# XibecaModule.net
KiCad netlist of a schematic drawn in EAGLE
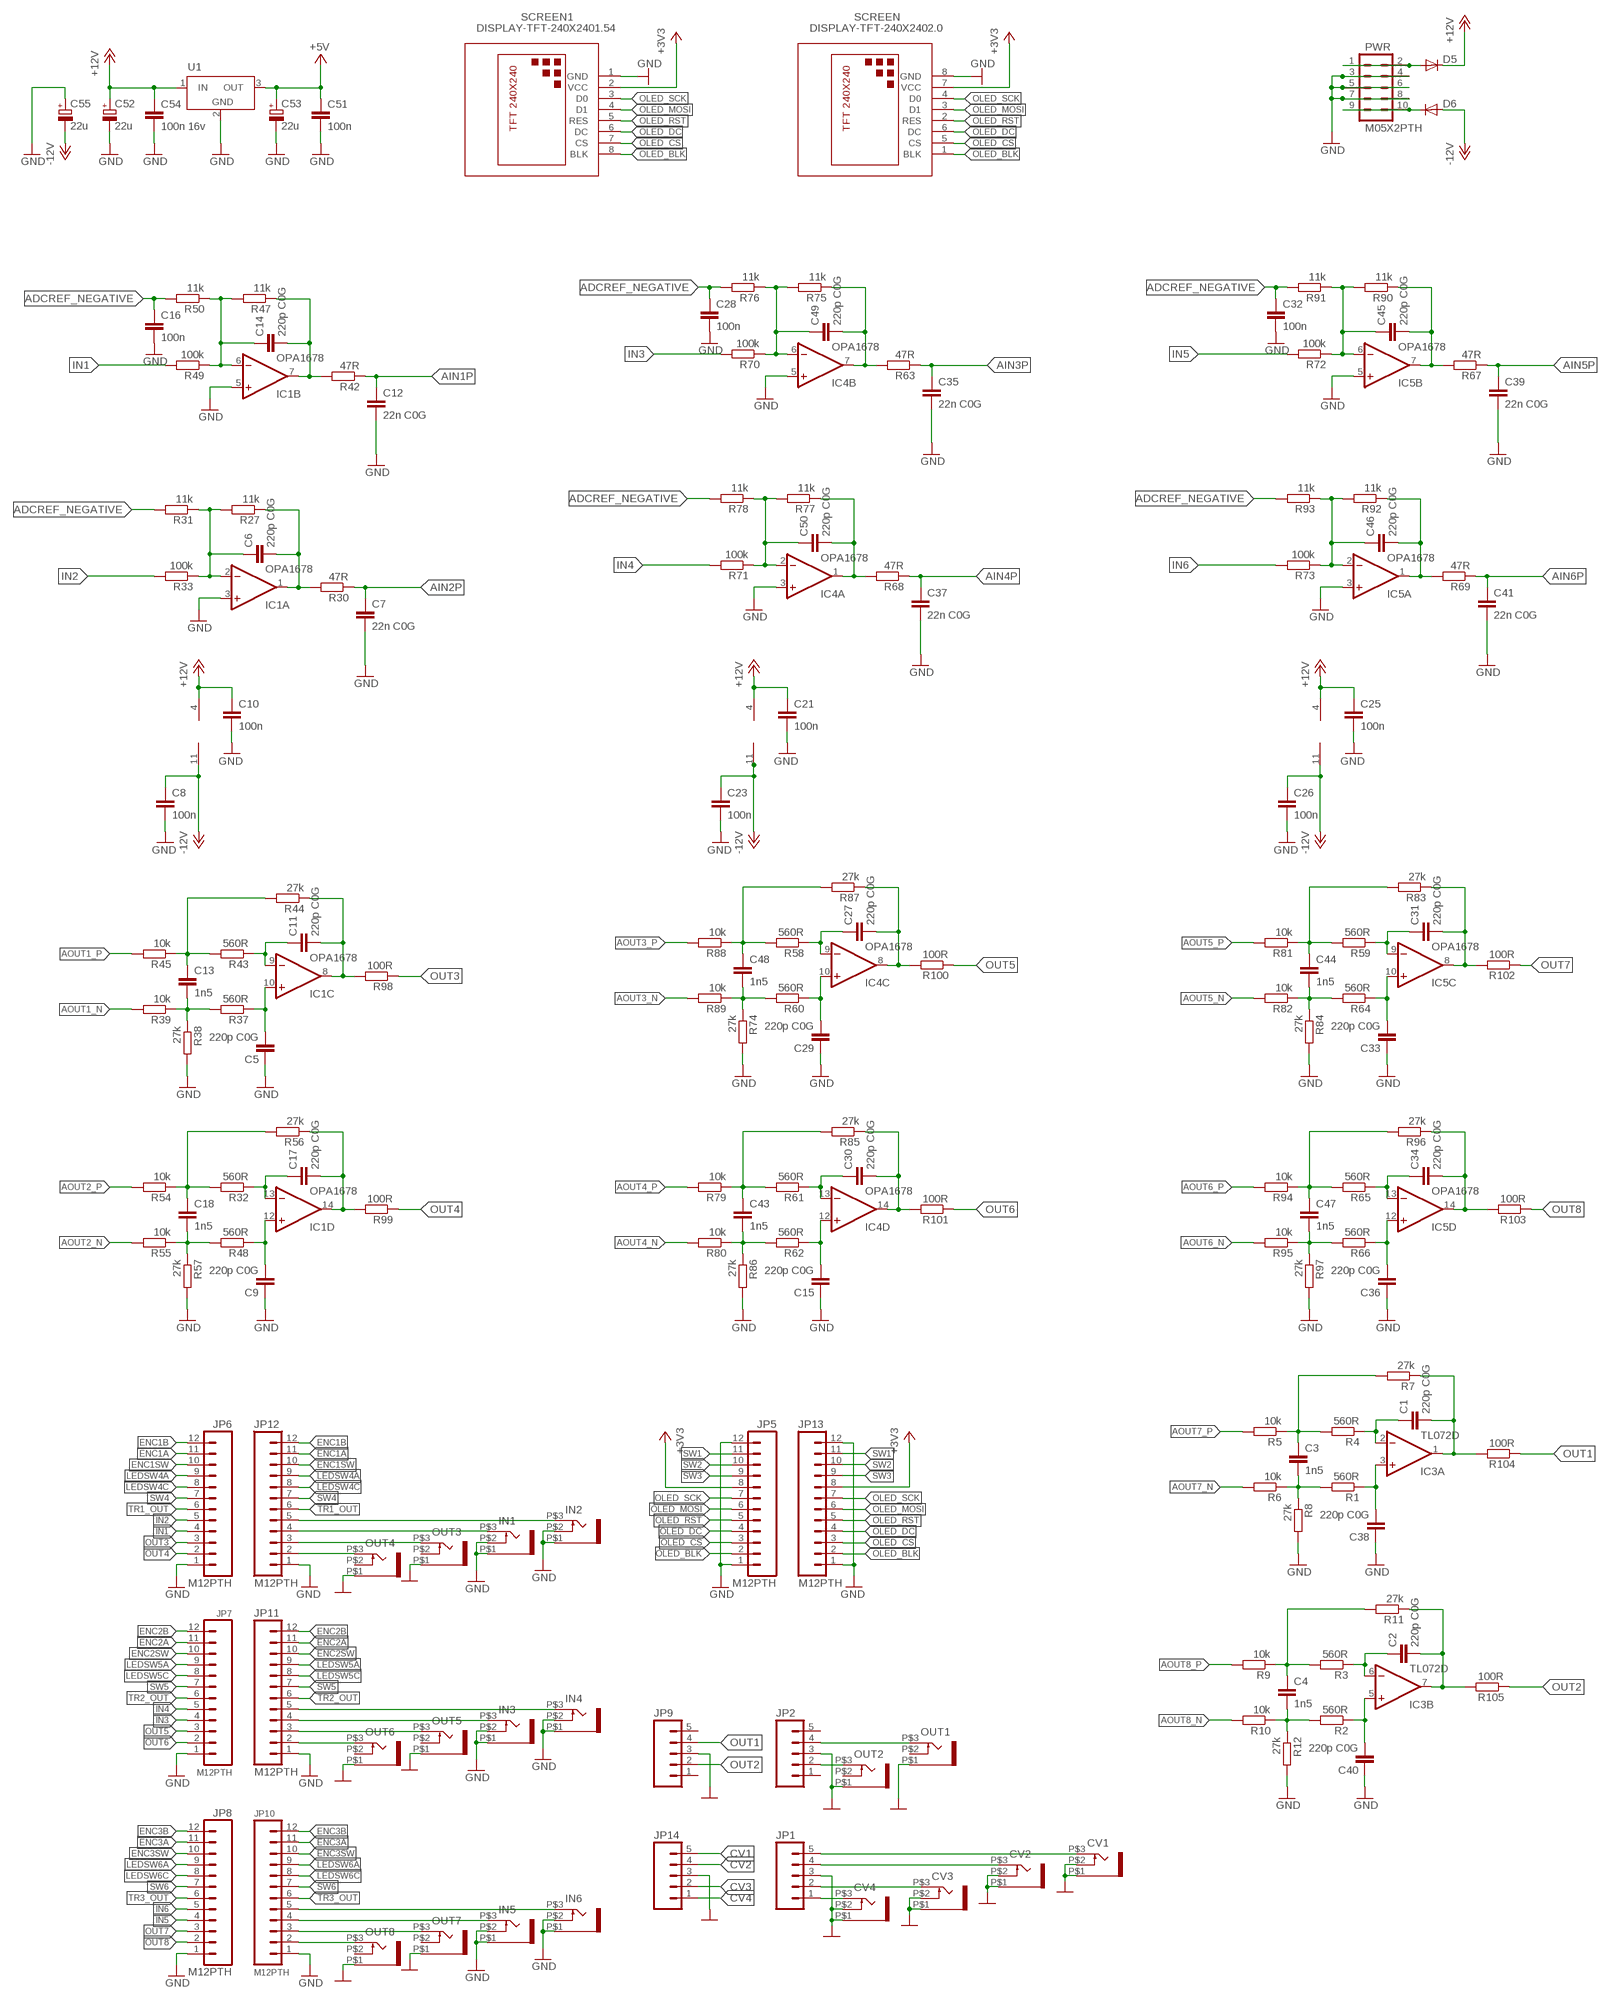
[diagram p0: schematic, sheet 1, part 1 of 2]
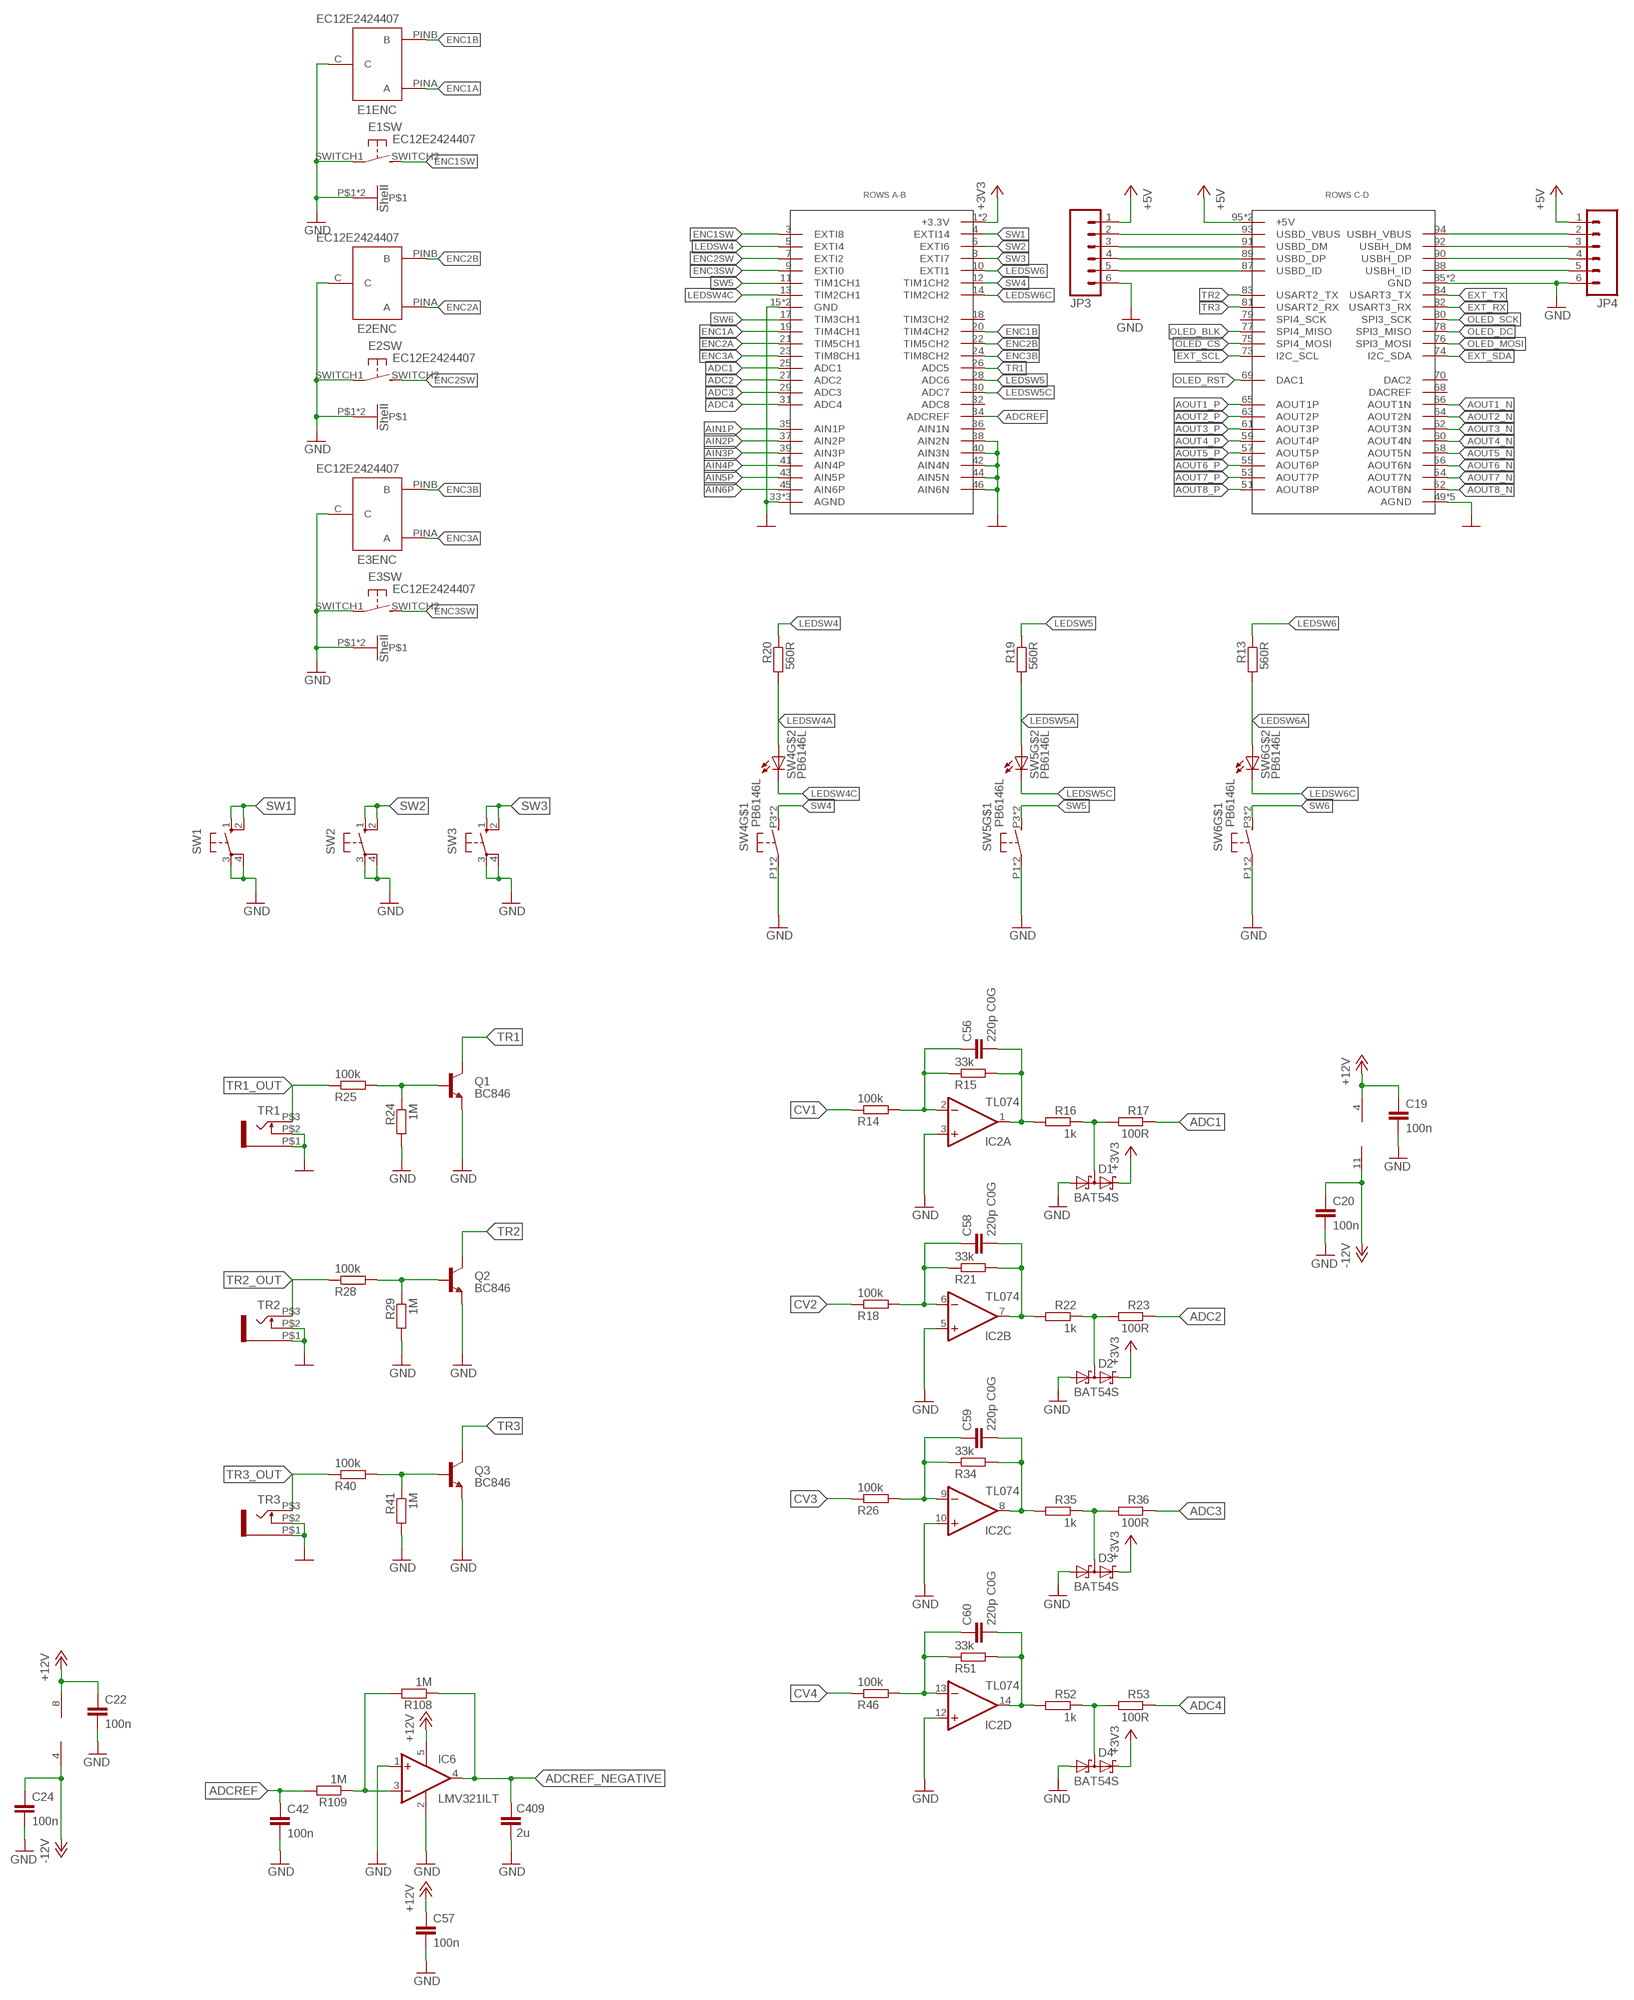
[diagram p1: schematic, sheet 1, part 2 of 2]

(export (version "E")
  (design (tool "Eeschema 10.0.6"))
  (components
    (comp (ref "C1")
      (value "220p C0G")
      (footprint "eagle-import:C0603")
      (libsource (lib "eagle-import") (part "Rebel_15457297_C-EUC0603"))
    )
    (comp (ref "C2")
      (value "220p C0G")
      (footprint "eagle-import:C0603")
      (libsource (lib "eagle-import") (part "Rebel_15457297_C-EUC0603"))
    )
    (comp (ref "C3")
      (value "1n5")
      (footprint "eagle-import:C0603")
      (libsource (lib "eagle-import") (part "Rebel_15457297_C-EUC0603"))
    )
    (comp (ref "C4")
      (value "1n5")
      (footprint "eagle-import:C0603")
      (libsource (lib "eagle-import") (part "Rebel_15457297_C-EUC0603"))
    )
    (comp (ref "C5")
      (value "220p C0G")
      (footprint "eagle-import:C0603")
      (libsource (lib "eagle-import") (part "Rebel_15457297_C-EUC0603"))
    )
    (comp (ref "C6")
      (value "220p C0G")
      (footprint "eagle-import:C0603")
      (libsource (lib "eagle-import") (part "Rebel_15457297_C-EUC0603"))
    )
    (comp (ref "C7")
      (value "22n C0G")
      (footprint "eagle-import:C0603")
      (libsource (lib "eagle-import") (part "Rebel_15457297_C-EUC0603"))
    )
    (comp (ref "C8")
      (value "100n")
      (footprint "eagle-import:C0603")
      (libsource (lib "eagle-import") (part "C-EUC0603"))
    )
    (comp (ref "C9")
      (value "220p C0G")
      (footprint "eagle-import:C0603")
      (libsource (lib "eagle-import") (part "Rebel_15457297_C-EUC0603"))
    )
    (comp (ref "C10")
      (value "100n")
      (footprint "eagle-import:C0603")
      (libsource (lib "eagle-import") (part "C-EUC0603"))
    )
    (comp (ref "C11")
      (value "220p C0G")
      (footprint "eagle-import:C0603")
      (libsource (lib "eagle-import") (part "Rebel_15457297_C-EUC0603"))
    )
    (comp (ref "C12")
      (value "22n C0G")
      (footprint "eagle-import:C0603")
      (libsource (lib "eagle-import") (part "Rebel_15457297_C-EUC0603"))
    )
    (comp (ref "C13")
      (value "1n5")
      (footprint "eagle-import:C0603")
      (libsource (lib "eagle-import") (part "Rebel_15457297_C-EUC0603"))
    )
    (comp (ref "C14")
      (value "220p C0G")
      (footprint "eagle-import:C0603")
      (libsource (lib "eagle-import") (part "Rebel_15457297_C-EUC0603"))
    )
    (comp (ref "C15")
      (value "220p C0G")
      (footprint "eagle-import:C0603")
      (libsource (lib "eagle-import") (part "Rebel_15457297_C-EUC0603"))
    )
    (comp (ref "C16")
      (value "100n")
      (footprint "eagle-import:C0603")
      (libsource (lib "eagle-import") (part "Rebel_15457297_C-EUC0603"))
    )
    (comp (ref "C17")
      (value "220p C0G")
      (footprint "eagle-import:C0603")
      (libsource (lib "eagle-import") (part "Rebel_15457297_C-EUC0603"))
    )
    (comp (ref "C18")
      (value "1n5")
      (footprint "eagle-import:C0603")
      (libsource (lib "eagle-import") (part "Rebel_15457297_C-EUC0603"))
    )
    (comp (ref "C19")
      (value "100n")
      (footprint "eagle-import:C0603")
      (libsource (lib "eagle-import") (part "Rebel_15457297_C-EUC0603"))
    )
    (comp (ref "C20")
      (value "100n")
      (footprint "eagle-import:C0603")
      (libsource (lib "eagle-import") (part "Rebel_15457297_C-EUC0603"))
    )
    (comp (ref "C21")
      (value "100n")
      (footprint "eagle-import:C0603")
      (libsource (lib "eagle-import") (part "Rebel_15457297_C-EUC0603"))
    )
    (comp (ref "C22")
      (value "100n")
      (footprint "eagle-import:C0603")
      (libsource (lib "eagle-import") (part "Rebel_15457297_C-EUC0603"))
    )
    (comp (ref "C23")
      (value "100n")
      (footprint "eagle-import:C0603")
      (libsource (lib "eagle-import") (part "Rebel_15457297_C-EUC0603"))
    )
    (comp (ref "C24")
      (value "100n")
      (footprint "eagle-import:C0603")
      (libsource (lib "eagle-import") (part "Rebel_15457297_C-EUC0603"))
    )
    (comp (ref "C25")
      (value "100n")
      (footprint "eagle-import:C0603")
      (libsource (lib "eagle-import") (part "C-EUC0603"))
    )
    (comp (ref "C26")
      (value "100n")
      (footprint "eagle-import:C0603")
      (libsource (lib "eagle-import") (part "C-EUC0603"))
    )
    (comp (ref "C27")
      (value "220p C0G")
      (footprint "eagle-import:C0603")
      (libsource (lib "eagle-import") (part "Rebel_15457297_C-EUC0603"))
    )
    (comp (ref "C28")
      (value "100n")
      (footprint "eagle-import:C0603")
      (libsource (lib "eagle-import") (part "Rebel_15457297_C-EUC0603"))
    )
    (comp (ref "C29")
      (value "220p C0G")
      (footprint "eagle-import:C0603")
      (libsource (lib "eagle-import") (part "Rebel_15457297_C-EUC0603"))
    )
    (comp (ref "C30")
      (value "220p C0G")
      (footprint "eagle-import:C0603")
      (libsource (lib "eagle-import") (part "Rebel_15457297_C-EUC0603"))
    )
    (comp (ref "C31")
      (value "220p C0G")
      (footprint "eagle-import:C0603")
      (libsource (lib "eagle-import") (part "Rebel_15457297_C-EUC0603"))
    )
    (comp (ref "C32")
      (value "100n")
      (footprint "eagle-import:C0603")
      (libsource (lib "eagle-import") (part "Rebel_15457297_C-EUC0603"))
    )
    (comp (ref "C33")
      (value "220p C0G")
      (footprint "eagle-import:C0603")
      (libsource (lib "eagle-import") (part "Rebel_15457297_C-EUC0603"))
    )
    (comp (ref "C34")
      (value "220p C0G")
      (footprint "eagle-import:C0603")
      (libsource (lib "eagle-import") (part "Rebel_15457297_C-EUC0603"))
    )
    (comp (ref "C35")
      (value "22n C0G")
      (footprint "eagle-import:C0603")
      (libsource (lib "eagle-import") (part "Rebel_15457297_C-EUC0603"))
    )
    (comp (ref "C36")
      (value "220p C0G")
      (footprint "eagle-import:C0603")
      (libsource (lib "eagle-import") (part "Rebel_15457297_C-EUC0603"))
    )
    (comp (ref "C37")
      (value "22n C0G")
      (footprint "eagle-import:C0603")
      (libsource (lib "eagle-import") (part "Rebel_15457297_C-EUC0603"))
    )
    (comp (ref "C38")
      (value "220p C0G")
      (footprint "eagle-import:C0603")
      (libsource (lib "eagle-import") (part "Rebel_15457297_C-EUC0603"))
    )
    (comp (ref "C39")
      (value "22n C0G")
      (footprint "eagle-import:C0603")
      (libsource (lib "eagle-import") (part "Rebel_15457297_C-EUC0603"))
    )
    (comp (ref "C40")
      (value "220p C0G")
      (footprint "eagle-import:C0603")
      (libsource (lib "eagle-import") (part "Rebel_15457297_C-EUC0603"))
    )
    (comp (ref "C41")
      (value "22n C0G")
      (footprint "eagle-import:C0603")
      (libsource (lib "eagle-import") (part "Rebel_15457297_C-EUC0603"))
    )
    (comp (ref "C42")
      (value "100n")
      (footprint "eagle-import:C0603")
      (libsource (lib "eagle-import") (part "Rebel_15457297_C-EUC0603"))
    )
    (comp (ref "C43")
      (value "1n5")
      (footprint "eagle-import:C0603")
      (libsource (lib "eagle-import") (part "Rebel_15457297_C-EUC0603"))
    )
    (comp (ref "C44")
      (value "1n5")
      (footprint "eagle-import:C0603")
      (libsource (lib "eagle-import") (part "Rebel_15457297_C-EUC0603"))
    )
    (comp (ref "C45")
      (value "220p C0G")
      (footprint "eagle-import:C0603")
      (libsource (lib "eagle-import") (part "Rebel_15457297_C-EUC0603"))
    )
    (comp (ref "C46")
      (value "220p C0G")
      (footprint "eagle-import:C0603")
      (libsource (lib "eagle-import") (part "Rebel_15457297_C-EUC0603"))
    )
    (comp (ref "C47")
      (value "1n5")
      (footprint "eagle-import:C0603")
      (libsource (lib "eagle-import") (part "Rebel_15457297_C-EUC0603"))
    )
    (comp (ref "C48")
      (value "1n5")
      (footprint "eagle-import:C0603")
      (libsource (lib "eagle-import") (part "Rebel_15457297_C-EUC0603"))
    )
    (comp (ref "C49")
      (value "220p C0G")
      (footprint "eagle-import:C0603")
      (libsource (lib "eagle-import") (part "Rebel_15457297_C-EUC0603"))
    )
    (comp (ref "C50")
      (value "220p C0G")
      (footprint "eagle-import:C0603")
      (libsource (lib "eagle-import") (part "Rebel_15457297_C-EUC0603"))
    )
    (comp (ref "C51")
      (value "100n")
      (footprint "eagle-import:C0603")
      (libsource (lib "eagle-import") (part "Rebel_15457297_C-EUC0603"))
    )
    (comp (ref "C52")
      (value "22u")
      (footprint "eagle-import:E5-8,5")
      (libsource (lib "eagle-import") (part "CPOL-EUE5-8.5"))
    )
    (comp (ref "C53")
      (value "22u")
      (footprint "eagle-import:E5-8,5")
      (libsource (lib "eagle-import") (part "CPOL-EUE5-8.5"))
    )
    (comp (ref "C54")
      (value "100n 16v")
      (footprint "eagle-import:C0603")
      (libsource (lib "eagle-import") (part "Rebel_15457297_C-EUC0603"))
    )
    (comp (ref "C55")
      (value "22u")
      (footprint "eagle-import:E5-8,5")
      (libsource (lib "eagle-import") (part "CPOL-EUE5-8.5"))
    )
    (comp (ref "C56")
      (value "220p C0G")
      (footprint "eagle-import:C0603")
      (libsource (lib "eagle-import") (part "Rebel_15457297_C-EUC0603"))
    )
    (comp (ref "C57")
      (value "100n")
      (footprint "eagle-import:C0603")
      (libsource (lib "eagle-import") (part "Rebel_15457297_C-EUC0603"))
    )
    (comp (ref "C58")
      (value "220p C0G")
      (footprint "eagle-import:C0603")
      (libsource (lib "eagle-import") (part "Rebel_15457297_C-EUC0603"))
    )
    (comp (ref "C59")
      (value "220p C0G")
      (footprint "eagle-import:C0603")
      (libsource (lib "eagle-import") (part "Rebel_15457297_C-EUC0603"))
    )
    (comp (ref "C60")
      (value "220p C0G")
      (footprint "eagle-import:C0603")
      (libsource (lib "eagle-import") (part "Rebel_15457297_C-EUC0603"))
    )
    (comp (ref "C409")
      (value "2u")
      (footprint "eagle-import:C0603")
      (libsource (lib "eagle-import") (part "C-EUC0603"))
    )
    (comp (ref "CV1")
      (value "THONKICONN")
      (footprint "eagle-import:THONKICONN")
      (libsource (lib "eagle-import") (part "THONKICONN"))
    )
    (comp (ref "CV2")
      (value "THONKICONN")
      (footprint "eagle-import:THONKICONN")
      (libsource (lib "eagle-import") (part "THONKICONN"))
    )
    (comp (ref "CV3")
      (value "THONKICONN")
      (footprint "eagle-import:THONKICONN")
      (libsource (lib "eagle-import") (part "THONKICONN"))
    )
    (comp (ref "CV4")
      (value "THONKICONN")
      (footprint "eagle-import:THONKICONN")
      (libsource (lib "eagle-import") (part "THONKICONN"))
    )
    (comp (ref "D1")
      (value "BAT54S")
      (footprint "eagle-import:SOT23")
      (libsource (lib "eagle-import") (part "BAT54S"))
    )
    (comp (ref "D2")
      (value "BAT54S")
      (footprint "eagle-import:SOT23")
      (libsource (lib "eagle-import") (part "BAT54S"))
    )
    (comp (ref "D3")
      (value "BAT54S")
      (footprint "eagle-import:SOT23")
      (libsource (lib "eagle-import") (part "BAT54S"))
    )
    (comp (ref "D4")
      (value "BAT54S")
      (footprint "eagle-import:SOT23")
      (libsource (lib "eagle-import") (part "BAT54S"))
    )
    (comp (ref "D5")
      (value "DIODE1N4001")
      (footprint "eagle-import:DIODE-1N4001")
      (libsource (lib "eagle-import") (part "DIODE1N4001"))
    )
    (comp (ref "D6")
      (value "DIODE1N4001")
      (footprint "eagle-import:DIODE-1N4001")
      (libsource (lib "eagle-import") (part "DIODE1N4001"))
    )
    (comp (ref "E1")
      (value "EC12E2424407")
      (footprint "eagle-import:EC12E2424407")
      (libsource (lib "eagle-import") (part "EC12E2424407"))
    )
    (comp (ref "E2")
      (value "EC12E2424407")
      (footprint "eagle-import:EC12E2424407")
      (libsource (lib "eagle-import") (part "EC12E2424407"))
    )
    (comp (ref "E3")
      (value "EC12E2424407")
      (footprint "eagle-import:EC12E2424407")
      (libsource (lib "eagle-import") (part "EC12E2424407"))
    )
    (comp (ref "IC1")
      (value "OPA1678")
      (footprint "eagle-import:SO14")
      (libsource (lib "eagle-import") (part "TL074D"))
    )
    (comp (ref "IC2")
      (value "TL074")
      (footprint "eagle-import:SO14")
      (libsource (lib "eagle-import") (part "QUAD_OPAMPD"))
    )
    (comp (ref "IC3")
      (value "TL072D")
      (footprint "eagle-import:SO08")
      (libsource (lib "eagle-import") (part "TL072D"))
    )
    (comp (ref "IC4")
      (value "OPA1678")
      (footprint "eagle-import:SO14")
      (libsource (lib "eagle-import") (part "TL074D"))
    )
    (comp (ref "IC5")
      (value "OPA1678")
      (footprint "eagle-import:SO14")
      (libsource (lib "eagle-import") (part "TL074D"))
    )
    (comp (ref "IC6")
      (value "LMV321ILT")
      (footprint "eagle-import:SOT23-5")
      (libsource (lib "eagle-import") (part "LM321?MF"))
    )
    (comp (ref "IN1")
      (value "THONKICONN")
      (footprint "eagle-import:THONKICONN")
      (libsource (lib "eagle-import") (part "THONKICONN"))
    )
    (comp (ref "IN2")
      (value "THONKICONN")
      (footprint "eagle-import:THONKICONN")
      (libsource (lib "eagle-import") (part "THONKICONN"))
    )
    (comp (ref "IN3")
      (value "THONKICONN")
      (footprint "eagle-import:THONKICONN")
      (libsource (lib "eagle-import") (part "THONKICONN"))
    )
    (comp (ref "IN4")
      (value "THONKICONN")
      (footprint "eagle-import:THONKICONN")
      (libsource (lib "eagle-import") (part "THONKICONN"))
    )
    (comp (ref "IN5")
      (value "THONKICONN")
      (footprint "eagle-import:THONKICONN")
      (libsource (lib "eagle-import") (part "THONKICONN"))
    )
    (comp (ref "IN6")
      (value "THONKICONN")
      (footprint "eagle-import:THONKICONN")
      (libsource (lib "eagle-import") (part "THONKICONN"))
    )
    (comp (ref "JP1")
      (value "M05PTH")
      (footprint "eagle-import:1X05")
      (libsource (lib "eagle-import") (part "M05PTH"))
    )
    (comp (ref "JP2")
      (value "M05PTH")
      (footprint "eagle-import:1X05")
      (libsource (lib "eagle-import") (part "M05PTH"))
    )
    (comp (ref "JP3")
      (value "M06SIP")
      (footprint "eagle-import:1X06")
      (libsource (lib "eagle-import") (part "M06SIP"))
    )
    (comp (ref "JP4")
      (value "M06SIP")
      (footprint "eagle-import:1X06")
      (libsource (lib "eagle-import") (part "M06SIP"))
    )
    (comp (ref "JP5")
      (value "M12PTH")
      (footprint "eagle-import:1X12")
      (libsource (lib "eagle-import") (part "M12PTH"))
    )
    (comp (ref "JP6")
      (value "M12PTH")
      (footprint "eagle-import:1X12")
      (libsource (lib "eagle-import") (part "M12PTH"))
    )
    (comp (ref "JP7")
      (value "M12PTH")
      (footprint "eagle-import:1X12")
      (libsource (lib "eagle-import") (part "M12PTH"))
    )
    (comp (ref "JP8")
      (value "M12PTH")
      (footprint "eagle-import:1X12")
      (libsource (lib "eagle-import") (part "M12PTH"))
    )
    (comp (ref "JP9")
      (value "M05PTH")
      (footprint "eagle-import:1X05")
      (libsource (lib "eagle-import") (part "M05PTH"))
    )
    (comp (ref "JP10")
      (value "M12PTH")
      (footprint "eagle-import:1X12")
      (libsource (lib "eagle-import") (part "M12PTH"))
    )
    (comp (ref "JP11")
      (value "M12PTH")
      (footprint "eagle-import:1X12")
      (libsource (lib "eagle-import") (part "M12PTH"))
    )
    (comp (ref "JP12")
      (value "M12PTH")
      (footprint "eagle-import:1X12")
      (libsource (lib "eagle-import") (part "M12PTH"))
    )
    (comp (ref "JP13")
      (value "M12PTH")
      (footprint "eagle-import:1X12")
      (libsource (lib "eagle-import") (part "M12PTH"))
    )
    (comp (ref "JP14")
      (value "M05PTH")
      (footprint "eagle-import:1X05")
      (libsource (lib "eagle-import") (part "M05PTH"))
    )
    (comp (ref "OUT1")
      (value "THONKICONN")
      (footprint "eagle-import:THONKICONN")
      (libsource (lib "eagle-import") (part "THONKICONN"))
    )
    (comp (ref "OUT2")
      (value "THONKICONN")
      (footprint "eagle-import:THONKICONN")
      (libsource (lib "eagle-import") (part "THONKICONN"))
    )
    (comp (ref "OUT3")
      (value "THONKICONN")
      (footprint "eagle-import:THONKICONN")
      (libsource (lib "eagle-import") (part "THONKICONN"))
    )
    (comp (ref "OUT4")
      (value "THONKICONN")
      (footprint "eagle-import:THONKICONN")
      (libsource (lib "eagle-import") (part "THONKICONN"))
    )
    (comp (ref "OUT5")
      (value "THONKICONN")
      (footprint "eagle-import:THONKICONN")
      (libsource (lib "eagle-import") (part "THONKICONN"))
    )
    (comp (ref "OUT6")
      (value "THONKICONN")
      (footprint "eagle-import:THONKICONN")
      (libsource (lib "eagle-import") (part "THONKICONN"))
    )
    (comp (ref "OUT7")
      (value "THONKICONN")
      (footprint "eagle-import:THONKICONN")
      (libsource (lib "eagle-import") (part "THONKICONN"))
    )
    (comp (ref "OUT8")
      (value "THONKICONN")
      (footprint "eagle-import:THONKICONN")
      (libsource (lib "eagle-import") (part "THONKICONN"))
    )
    (comp (ref "PWR")
      (value "M05X2PTH")
      (footprint "eagle-import:AVR_ICSP")
      (libsource (lib "eagle-import") (part "M05X2PTH"))
    )
    (comp (ref "Q1")
      (value "BC846")
      (footprint "eagle-import:SOT23")
      (libsource (lib "eagle-import") (part "BC846"))
    )
    (comp (ref "Q2")
      (value "BC846")
      (footprint "eagle-import:SOT23")
      (libsource (lib "eagle-import") (part "BC846"))
    )
    (comp (ref "Q3")
      (value "BC846")
      (footprint "eagle-import:SOT23")
      (libsource (lib "eagle-import") (part "BC846"))
    )
    (comp (ref "R1")
      (value "560R")
      (footprint "eagle-import:R0603")
      (libsource (lib "eagle-import") (part "rcl_334_R-EU_R0603"))
    )
    (comp (ref "R2")
      (value "560R")
      (footprint "eagle-import:R0603")
      (libsource (lib "eagle-import") (part "rcl_334_R-EU_R0603"))
    )
    (comp (ref "R3")
      (value "560R")
      (footprint "eagle-import:R0603")
      (libsource (lib "eagle-import") (part "rcl_334_R-EU_R0603"))
    )
    (comp (ref "R4")
      (value "560R")
      (footprint "eagle-import:R0603")
      (libsource (lib "eagle-import") (part "rcl_334_R-EU_R0603"))
    )
    (comp (ref "R5")
      (value "10k")
      (footprint "eagle-import:R0603")
      (libsource (lib "eagle-import") (part "rcl_334_R-EU_R0603"))
    )
    (comp (ref "R6")
      (value "10k")
      (footprint "eagle-import:R0603")
      (libsource (lib "eagle-import") (part "rcl_334_R-EU_R0603"))
    )
    (comp (ref "R7")
      (value "27k")
      (footprint "eagle-import:R0603")
      (libsource (lib "eagle-import") (part "rcl_334_R-EU_R0603"))
    )
    (comp (ref "R8")
      (value "27k")
      (footprint "eagle-import:R0603")
      (libsource (lib "eagle-import") (part "rcl_334_R-EU_R0603"))
    )
    (comp (ref "R9")
      (value "10k")
      (footprint "eagle-import:R0603")
      (libsource (lib "eagle-import") (part "rcl_334_R-EU_R0603"))
    )
    (comp (ref "R10")
      (value "10k")
      (footprint "eagle-import:R0603")
      (libsource (lib "eagle-import") (part "rcl_334_R-EU_R0603"))
    )
    (comp (ref "R11")
      (value "27k")
      (footprint "eagle-import:R0603")
      (libsource (lib "eagle-import") (part "rcl_334_R-EU_R0603"))
    )
    (comp (ref "R12")
      (value "27k")
      (footprint "eagle-import:R0603")
      (libsource (lib "eagle-import") (part "rcl_334_R-EU_R0603"))
    )
    (comp (ref "R13")
      (value "560R")
      (footprint "eagle-import:0603")
      (libsource (lib "eagle-import") (part "R-EU_R0603"))
    )
    (comp (ref "R14")
      (value "100k")
      (footprint "eagle-import:0603")
      (libsource (lib "eagle-import") (part "R-EU_0603"))
    )
    (comp (ref "R15")
      (value "33k")
      (footprint "eagle-import:0603")
      (libsource (lib "eagle-import") (part "R-EU_0603"))
    )
    (comp (ref "R16")
      (value "1k")
      (footprint "eagle-import:0603")
      (libsource (lib "eagle-import") (part "R-EU_0603"))
    )
    (comp (ref "R17")
      (value "100R")
      (footprint "eagle-import:0603")
      (libsource (lib "eagle-import") (part "R-EU_0603"))
    )
    (comp (ref "R18")
      (value "100k")
      (footprint "eagle-import:0603")
      (libsource (lib "eagle-import") (part "R-EU_0603"))
    )
    (comp (ref "R19")
      (value "560R")
      (footprint "eagle-import:0603")
      (libsource (lib "eagle-import") (part "R-EU_R0603"))
    )
    (comp (ref "R20")
      (value "560R")
      (footprint "eagle-import:0603")
      (libsource (lib "eagle-import") (part "R-EU_R0603"))
    )
    (comp (ref "R21")
      (value "33k")
      (footprint "eagle-import:0603")
      (libsource (lib "eagle-import") (part "R-EU_0603"))
    )
    (comp (ref "R22")
      (value "1k")
      (footprint "eagle-import:0603")
      (libsource (lib "eagle-import") (part "R-EU_0603"))
    )
    (comp (ref "R23")
      (value "100R")
      (footprint "eagle-import:0603")
      (libsource (lib "eagle-import") (part "R-EU_0603"))
    )
    (comp (ref "R24")
      (value "1M")
      (footprint "eagle-import:0603")
      (libsource (lib "eagle-import") (part "R-EU_R0603"))
    )
    (comp (ref "R25")
      (value "100k")
      (footprint "eagle-import:0603")
      (libsource (lib "eagle-import") (part "R-EU_R0603"))
    )
    (comp (ref "R26")
      (value "100k")
      (footprint "eagle-import:0603")
      (libsource (lib "eagle-import") (part "R-EU_0603"))
    )
    (comp (ref "R27")
      (value "11k")
      (footprint "eagle-import:R0603")
      (libsource (lib "eagle-import") (part "rcl_334_R-EU_R0603"))
    )
    (comp (ref "R28")
      (value "100k")
      (footprint "eagle-import:0603")
      (libsource (lib "eagle-import") (part "R-EU_R0603"))
    )
    (comp (ref "R29")
      (value "1M")
      (footprint "eagle-import:0603")
      (libsource (lib "eagle-import") (part "R-EU_R0603"))
    )
    (comp (ref "R30")
      (value "47R")
      (footprint "eagle-import:R0603")
      (libsource (lib "eagle-import") (part "rcl_334_R-EU_R0603"))
    )
    (comp (ref "R31")
      (value "11k")
      (footprint "eagle-import:R0603")
      (libsource (lib "eagle-import") (part "rcl_334_R-EU_R0603"))
    )
    (comp (ref "R32")
      (value "560R")
      (footprint "eagle-import:R0603")
      (libsource (lib "eagle-import") (part "rcl_334_R-EU_R0603"))
    )
    (comp (ref "R33")
      (value "100k")
      (footprint "eagle-import:R0603")
      (libsource (lib "eagle-import") (part "rcl_334_R-EU_R0603"))
    )
    (comp (ref "R34")
      (value "33k")
      (footprint "eagle-import:0603")
      (libsource (lib "eagle-import") (part "R-EU_0603"))
    )
    (comp (ref "R35")
      (value "1k")
      (footprint "eagle-import:0603")
      (libsource (lib "eagle-import") (part "R-EU_0603"))
    )
    (comp (ref "R36")
      (value "100R")
      (footprint "eagle-import:0603")
      (libsource (lib "eagle-import") (part "R-EU_0603"))
    )
    (comp (ref "R37")
      (value "560R")
      (footprint "eagle-import:R0603")
      (libsource (lib "eagle-import") (part "rcl_334_R-EU_R0603"))
    )
    (comp (ref "R38")
      (value "27k")
      (footprint "eagle-import:R0603")
      (libsource (lib "eagle-import") (part "rcl_334_R-EU_R0603"))
    )
    (comp (ref "R39")
      (value "10k")
      (footprint "eagle-import:R0603")
      (libsource (lib "eagle-import") (part "rcl_334_R-EU_R0603"))
    )
    (comp (ref "R40")
      (value "100k")
      (footprint "eagle-import:0603")
      (libsource (lib "eagle-import") (part "R-EU_R0603"))
    )
    (comp (ref "R41")
      (value "1M")
      (footprint "eagle-import:0603")
      (libsource (lib "eagle-import") (part "R-EU_R0603"))
    )
    (comp (ref "R42")
      (value "47R")
      (footprint "eagle-import:R0603")
      (libsource (lib "eagle-import") (part "rcl_334_R-EU_R0603"))
    )
    (comp (ref "R43")
      (value "560R")
      (footprint "eagle-import:R0603")
      (libsource (lib "eagle-import") (part "rcl_334_R-EU_R0603"))
    )
    (comp (ref "R44")
      (value "27k")
      (footprint "eagle-import:R0603")
      (libsource (lib "eagle-import") (part "rcl_334_R-EU_R0603"))
    )
    (comp (ref "R45")
      (value "10k")
      (footprint "eagle-import:R0603")
      (libsource (lib "eagle-import") (part "rcl_334_R-EU_R0603"))
    )
    (comp (ref "R46")
      (value "100k")
      (footprint "eagle-import:0603")
      (libsource (lib "eagle-import") (part "R-EU_0603"))
    )
    (comp (ref "R47")
      (value "11k")
      (footprint "eagle-import:R0603")
      (libsource (lib "eagle-import") (part "rcl_334_R-EU_R0603"))
    )
    (comp (ref "R48")
      (value "560R")
      (footprint "eagle-import:R0603")
      (libsource (lib "eagle-import") (part "rcl_334_R-EU_R0603"))
    )
    (comp (ref "R49")
      (value "100k")
      (footprint "eagle-import:R0603")
      (libsource (lib "eagle-import") (part "rcl_334_R-EU_R0603"))
    )
    (comp (ref "R50")
      (value "11k")
      (footprint "eagle-import:R0603")
      (libsource (lib "eagle-import") (part "rcl_334_R-EU_R0603"))
    )
    (comp (ref "R51")
      (value "33k")
      (footprint "eagle-import:0603")
      (libsource (lib "eagle-import") (part "R-EU_0603"))
    )
    (comp (ref "R52")
      (value "1k")
      (footprint "eagle-import:0603")
      (libsource (lib "eagle-import") (part "R-EU_0603"))
    )
    (comp (ref "R53")
      (value "100R")
      (footprint "eagle-import:0603")
      (libsource (lib "eagle-import") (part "R-EU_0603"))
    )
    (comp (ref "R54")
      (value "10k")
      (footprint "eagle-import:R0603")
      (libsource (lib "eagle-import") (part "rcl_334_R-EU_R0603"))
    )
    (comp (ref "R55")
      (value "10k")
      (footprint "eagle-import:R0603")
      (libsource (lib "eagle-import") (part "rcl_334_R-EU_R0603"))
    )
    (comp (ref "R56")
      (value "27k")
      (footprint "eagle-import:R0603")
      (libsource (lib "eagle-import") (part "rcl_334_R-EU_R0603"))
    )
    (comp (ref "R57")
      (value "27k")
      (footprint "eagle-import:R0603")
      (libsource (lib "eagle-import") (part "rcl_334_R-EU_R0603"))
    )
    (comp (ref "R58")
      (value "560R")
      (footprint "eagle-import:R0603")
      (libsource (lib "eagle-import") (part "rcl_334_R-EU_R0603"))
    )
    (comp (ref "R59")
      (value "560R")
      (footprint "eagle-import:R0603")
      (libsource (lib "eagle-import") (part "rcl_334_R-EU_R0603"))
    )
    (comp (ref "R60")
      (value "560R")
      (footprint "eagle-import:R0603")
      (libsource (lib "eagle-import") (part "rcl_334_R-EU_R0603"))
    )
    (comp (ref "R61")
      (value "560R")
      (footprint "eagle-import:R0603")
      (libsource (lib "eagle-import") (part "rcl_334_R-EU_R0603"))
    )
    (comp (ref "R62")
      (value "560R")
      (footprint "eagle-import:R0603")
      (libsource (lib "eagle-import") (part "rcl_334_R-EU_R0603"))
    )
    (comp (ref "R63")
      (value "47R")
      (footprint "eagle-import:R0603")
      (libsource (lib "eagle-import") (part "rcl_334_R-EU_R0603"))
    )
    (comp (ref "R64")
      (value "560R")
      (footprint "eagle-import:R0603")
      (libsource (lib "eagle-import") (part "rcl_334_R-EU_R0603"))
    )
    (comp (ref "R65")
      (value "560R")
      (footprint "eagle-import:R0603")
      (libsource (lib "eagle-import") (part "rcl_334_R-EU_R0603"))
    )
    (comp (ref "R66")
      (value "560R")
      (footprint "eagle-import:R0603")
      (libsource (lib "eagle-import") (part "rcl_334_R-EU_R0603"))
    )
    (comp (ref "R67")
      (value "47R")
      (footprint "eagle-import:R0603")
      (libsource (lib "eagle-import") (part "rcl_334_R-EU_R0603"))
    )
    (comp (ref "R68")
      (value "47R")
      (footprint "eagle-import:R0603")
      (libsource (lib "eagle-import") (part "rcl_334_R-EU_R0603"))
    )
    (comp (ref "R69")
      (value "47R")
      (footprint "eagle-import:R0603")
      (libsource (lib "eagle-import") (part "rcl_334_R-EU_R0603"))
    )
    (comp (ref "R70")
      (value "100k")
      (footprint "eagle-import:R0603")
      (libsource (lib "eagle-import") (part "rcl_334_R-EU_R0603"))
    )
    (comp (ref "R71")
      (value "100k")
      (footprint "eagle-import:R0603")
      (libsource (lib "eagle-import") (part "rcl_334_R-EU_R0603"))
    )
    (comp (ref "R72")
      (value "100k")
      (footprint "eagle-import:R0603")
      (libsource (lib "eagle-import") (part "rcl_334_R-EU_R0603"))
    )
    (comp (ref "R73")
      (value "100k")
      (footprint "eagle-import:R0603")
      (libsource (lib "eagle-import") (part "rcl_334_R-EU_R0603"))
    )
    (comp (ref "R74")
      (value "27k")
      (footprint "eagle-import:R0603")
      (libsource (lib "eagle-import") (part "rcl_334_R-EU_R0603"))
    )
    (comp (ref "R75")
      (value "11k")
      (footprint "eagle-import:R0603")
      (libsource (lib "eagle-import") (part "rcl_334_R-EU_R0603"))
    )
    (comp (ref "R76")
      (value "11k")
      (footprint "eagle-import:R0603")
      (libsource (lib "eagle-import") (part "rcl_334_R-EU_R0603"))
    )
    (comp (ref "R77")
      (value "11k")
      (footprint "eagle-import:R0603")
      (libsource (lib "eagle-import") (part "rcl_334_R-EU_R0603"))
    )
    (comp (ref "R78")
      (value "11k")
      (footprint "eagle-import:R0603")
      (libsource (lib "eagle-import") (part "rcl_334_R-EU_R0603"))
    )
    (comp (ref "R79")
      (value "10k")
      (footprint "eagle-import:R0603")
      (libsource (lib "eagle-import") (part "rcl_334_R-EU_R0603"))
    )
    (comp (ref "R80")
      (value "10k")
      (footprint "eagle-import:R0603")
      (libsource (lib "eagle-import") (part "rcl_334_R-EU_R0603"))
    )
    (comp (ref "R81")
      (value "10k")
      (footprint "eagle-import:R0603")
      (libsource (lib "eagle-import") (part "rcl_334_R-EU_R0603"))
    )
    (comp (ref "R82")
      (value "10k")
      (footprint "eagle-import:R0603")
      (libsource (lib "eagle-import") (part "rcl_334_R-EU_R0603"))
    )
    (comp (ref "R83")
      (value "27k")
      (footprint "eagle-import:R0603")
      (libsource (lib "eagle-import") (part "rcl_334_R-EU_R0603"))
    )
    (comp (ref "R84")
      (value "27k")
      (footprint "eagle-import:R0603")
      (libsource (lib "eagle-import") (part "rcl_334_R-EU_R0603"))
    )
    (comp (ref "R85")
      (value "27k")
      (footprint "eagle-import:R0603")
      (libsource (lib "eagle-import") (part "rcl_334_R-EU_R0603"))
    )
    (comp (ref "R86")
      (value "27k")
      (footprint "eagle-import:R0603")
      (libsource (lib "eagle-import") (part "rcl_334_R-EU_R0603"))
    )
    (comp (ref "R87")
      (value "27k")
      (footprint "eagle-import:R0603")
      (libsource (lib "eagle-import") (part "rcl_334_R-EU_R0603"))
    )
    (comp (ref "R88")
      (value "10k")
      (footprint "eagle-import:R0603")
      (libsource (lib "eagle-import") (part "rcl_334_R-EU_R0603"))
    )
    (comp (ref "R89")
      (value "10k")
      (footprint "eagle-import:R0603")
      (libsource (lib "eagle-import") (part "rcl_334_R-EU_R0603"))
    )
    (comp (ref "R90")
      (value "11k")
      (footprint "eagle-import:R0603")
      (libsource (lib "eagle-import") (part "rcl_334_R-EU_R0603"))
    )
    (comp (ref "R91")
      (value "11k")
      (footprint "eagle-import:R0603")
      (libsource (lib "eagle-import") (part "rcl_334_R-EU_R0603"))
    )
    (comp (ref "R92")
      (value "11k")
      (footprint "eagle-import:R0603")
      (libsource (lib "eagle-import") (part "rcl_334_R-EU_R0603"))
    )
    (comp (ref "R93")
      (value "11k")
      (footprint "eagle-import:R0603")
      (libsource (lib "eagle-import") (part "rcl_334_R-EU_R0603"))
    )
    (comp (ref "R94")
      (value "10k")
      (footprint "eagle-import:R0603")
      (libsource (lib "eagle-import") (part "rcl_334_R-EU_R0603"))
    )
    (comp (ref "R95")
      (value "10k")
      (footprint "eagle-import:R0603")
      (libsource (lib "eagle-import") (part "rcl_334_R-EU_R0603"))
    )
    (comp (ref "R96")
      (value "27k")
      (footprint "eagle-import:R0603")
      (libsource (lib "eagle-import") (part "rcl_334_R-EU_R0603"))
    )
    (comp (ref "R97")
      (value "27k")
      (footprint "eagle-import:R0603")
      (libsource (lib "eagle-import") (part "rcl_334_R-EU_R0603"))
    )
    (comp (ref "R98")
      (value "100R")
      (footprint "eagle-import:R0603")
      (libsource (lib "eagle-import") (part "rcl_334_R-EU_R0603"))
    )
    (comp (ref "R99")
      (value "100R")
      (footprint "eagle-import:R0603")
      (libsource (lib "eagle-import") (part "rcl_334_R-EU_R0603"))
    )
    (comp (ref "R100")
      (value "100R")
      (footprint "eagle-import:R0603")
      (libsource (lib "eagle-import") (part "rcl_334_R-EU_R0603"))
    )
    (comp (ref "R101")
      (value "100R")
      (footprint "eagle-import:R0603")
      (libsource (lib "eagle-import") (part "rcl_334_R-EU_R0603"))
    )
    (comp (ref "R102")
      (value "100R")
      (footprint "eagle-import:R0603")
      (libsource (lib "eagle-import") (part "rcl_334_R-EU_R0603"))
    )
    (comp (ref "R103")
      (value "100R")
      (footprint "eagle-import:R0603")
      (libsource (lib "eagle-import") (part "rcl_334_R-EU_R0603"))
    )
    (comp (ref "R104")
      (value "100R")
      (footprint "eagle-import:R0603")
      (libsource (lib "eagle-import") (part "rcl_334_R-EU_R0603"))
    )
    (comp (ref "R105")
      (value "100R")
      (footprint "eagle-import:R0603")
      (libsource (lib "eagle-import") (part "rcl_334_R-EU_R0603"))
    )
    (comp (ref "R108")
      (value "1M")
      (footprint "eagle-import:R0603")
      (libsource (lib "eagle-import") (part "rcl_334_R-EU_R0603"))
    )
    (comp (ref "R109")
      (value "1M")
      (footprint "eagle-import:R0603")
      (libsource (lib "eagle-import") (part "rcl_334_R-EU_R0603"))
    )
    (comp (ref "SCREEN")
      (value "DISPLAY-TFT-240X2402.0")
      (footprint "eagle-import:DISPLAY-TFT-240X320-2.0_")
      (libsource (lib "eagle-import") (part "DISPLAY-TFT-240X2402.0"))
    )
    (comp (ref "SCREEN1")
      (value "DISPLAY-TFT-240X2401.54")
      (footprint "eagle-import:DISPLAY-TFT-240X240-1.54_")
      (libsource (lib "eagle-import") (part "DISPLAY-TFT-240X2401.54"))
    )
    (comp (ref "SW1")
      (value "10-XX")
      (footprint "eagle-import:B3F-10XX")
      (fields (field (name "MPN") "B3F-1000"))
      (libsource (lib "eagle-import") (part "10-XX"))
    )
    (comp (ref "SW2")
      (value "10-XX")
      (footprint "eagle-import:B3F-10XX")
      (fields (field (name "MPN") "B3F-1000"))
      (libsource (lib "eagle-import") (part "10-XX"))
    )
    (comp (ref "SW3")
      (value "10-XX")
      (footprint "eagle-import:B3F-10XX")
      (fields (field (name "MPN") "B3F-1000"))
      (libsource (lib "eagle-import") (part "10-XX"))
    )
    (comp (ref "SW4")
      (value "PB6146L")
      (footprint "eagle-import:PB6146L")
      (libsource (lib "eagle-import") (part "PB6146L"))
    )
    (comp (ref "SW5")
      (value "PB6146L")
      (footprint "eagle-import:PB6146L")
      (libsource (lib "eagle-import") (part "PB6146L"))
    )
    (comp (ref "SW6")
      (value "PB6146L")
      (footprint "eagle-import:PB6146L")
      (libsource (lib "eagle-import") (part "PB6146L"))
    )
    (comp (ref "TR1")
      (value "THONKICONN")
      (footprint "eagle-import:THONKICONN")
      (libsource (lib "eagle-import") (part "THONKICONN"))
    )
    (comp (ref "TR2")
      (value "THONKICONN")
      (footprint "eagle-import:THONKICONN")
      (libsource (lib "eagle-import") (part "THONKICONN"))
    )
    (comp (ref "TR3")
      (value "THONKICONN")
      (footprint "eagle-import:THONKICONN")
      (libsource (lib "eagle-import") (part "THONKICONN"))
    )
    (comp (ref "U$2")
      (value "NOCTUA2NOCTUA2")
      (footprint "eagle-import:NOCTUA")
      (libsource (lib "eagle-import") (part "NOCTUA2NOCTUA2"))
    )
    (comp (ref "U1")
      (value "TSR-1-2450")
      (footprint "eagle-import:TSR-1-2450")
      (libsource (lib "eagle-import") (part "TSR-1-2450"))
    )
  )
  (nets
    (net (code "1") (name "+3V3") (class "Default")
      (node (ref "D1") (pin "2") (pinfunction "C2_2") (pintype "passive"))
      (node (ref "D2") (pin "2") (pinfunction "C2_2") (pintype "passive"))
      (node (ref "D3") (pin "2") (pinfunction "C2_2") (pintype "passive"))
      (node (ref "D4") (pin "2") (pinfunction "C2_2") (pintype "passive"))
      (node (ref "JP13") (pin "8") (pinfunction "8_8") (pintype "passive"))
      (node (ref "JP5") (pin "8") (pinfunction "8_8") (pintype "passive"))
      (node (ref "SCREEN") (pin "7") (pinfunction "VCC_7") (pintype "power_in"))
      (node (ref "SCREEN1") (pin "2") (pinfunction "VCC_2") (pintype "power_in"))
      (node (ref "U$2") (pin "1") (pinfunction "+3.3V_1") (pintype "bidirectional"))
      (node (ref "U$2") (pin "2") (pinfunction "+3.3V_2") (pintype "bidirectional"))
    )
    (net (code "2") (name "+5V") (class "Default")
      (node (ref "C51") (pin "1") (pinfunction "1_1") (pintype "passive"))
      (node (ref "C53") (pin "+") (pinfunction "+_+") (pintype "passive"))
      (node (ref "JP3") (pin "1") (pinfunction "1_1") (pintype "passive"))
      (node (ref "JP4") (pin "1") (pinfunction "1_1") (pintype "passive"))
      (node (ref "U$2") (pin "95") (pinfunction "+5V_95") (pintype "bidirectional"))
      (node (ref "U$2") (pin "96") (pinfunction "+5V_96") (pintype "bidirectional"))
      (node (ref "U1") (pin "3") (pinfunction "OUT_3") (pintype "output"))
    )
    (net (code "3") (name "+12V") (class "Default")
      (node (ref "C10") (pin "1") (pinfunction "1_1") (pintype "passive"))
      (node (ref "C19") (pin "1") (pinfunction "1_1") (pintype "passive"))
      (node (ref "C21") (pin "1") (pinfunction "1_1") (pintype "passive"))
      (node (ref "C22") (pin "1") (pinfunction "1_1") (pintype "passive"))
      (node (ref "C25") (pin "1") (pinfunction "1_1") (pintype "passive"))
      (node (ref "C52") (pin "+") (pinfunction "+_+") (pintype "passive"))
      (node (ref "C54") (pin "1") (pinfunction "1_1") (pintype "passive"))
      (node (ref "C57") (pin "1") (pinfunction "1_1") (pintype "passive"))
      (node (ref "D5") (pin "C") (pinfunction "C_C") (pintype "passive"))
      (node (ref "IC1") (pin "4") (pinfunction "V+_4") (pintype "power_in"))
      (node (ref "IC2") (pin "4") (pinfunction "V+_4") (pintype "power_in"))
      (node (ref "IC3") (pin "8") (pinfunction "V+_8") (pintype "power_in"))
      (node (ref "IC4") (pin "4") (pinfunction "V+_4") (pintype "power_in"))
      (node (ref "IC5") (pin "4") (pinfunction "V+_4") (pintype "power_in"))
      (node (ref "IC6") (pin "5") (pinfunction "V+_5") (pintype "power_in"))
      (node (ref "U1") (pin "1") (pinfunction "IN_1") (pintype "input"))
    )
    (net (code "4") (name "-12V") (class "Default")
      (node (ref "C20") (pin "1") (pinfunction "1_1") (pintype "passive"))
      (node (ref "C23") (pin "1") (pinfunction "1_1") (pintype "passive"))
      (node (ref "C24") (pin "1") (pinfunction "1_1") (pintype "passive"))
      (node (ref "C26") (pin "1") (pinfunction "1_1") (pintype "passive"))
      (node (ref "C55") (pin "-") (pinfunction "-_-") (pintype "passive"))
      (node (ref "C8") (pin "1") (pinfunction "1_1") (pintype "passive"))
      (node (ref "D6") (pin "A") (pinfunction "A_A") (pintype "passive"))
      (node (ref "IC1") (pin "11") (pinfunction "V-_11") (pintype "power_in"))
      (node (ref "IC2") (pin "11") (pinfunction "V-_11") (pintype "power_in"))
      (node (ref "IC3") (pin "4") (pinfunction "V-_4") (pintype "power_in"))
      (node (ref "IC4") (pin "11") (pinfunction "V-_11") (pintype "power_in"))
      (node (ref "IC5") (pin "11") (pinfunction "V-_11") (pintype "power_in"))
    )
    (net (code "5") (name "ADC1") (class "Default")
      (node (ref "R17") (pin "1") (pinfunction "1_1") (pintype "passive"))
      (node (ref "U$2") (pin "25") (pinfunction "ADC1_25") (pintype "bidirectional"))
    )
    (net (code "6") (name "ADC2") (class "Default")
      (node (ref "R23") (pin "1") (pinfunction "1_1") (pintype "passive"))
      (node (ref "U$2") (pin "27") (pinfunction "ADC2_27") (pintype "bidirectional"))
    )
    (net (code "7") (name "ADC3") (class "Default")
      (node (ref "R36") (pin "1") (pinfunction "1_1") (pintype "passive"))
      (node (ref "U$2") (pin "29") (pinfunction "ADC3_29") (pintype "bidirectional"))
    )
    (net (code "8") (name "ADC4") (class "Default")
      (node (ref "R53") (pin "1") (pinfunction "1_1") (pintype "passive"))
      (node (ref "U$2") (pin "31") (pinfunction "ADC4_31") (pintype "bidirectional"))
    )
    (net (code "9") (name "ADCREF") (class "Default")
      (node (ref "C42") (pin "1") (pinfunction "1_1") (pintype "passive"))
      (node (ref "R109") (pin "2") (pinfunction "2_2") (pintype "passive"))
      (node (ref "U$2") (pin "34") (pinfunction "ADCREF_34") (pintype "bidirectional"))
    )
    (net (code "10") (name "ADCREF_NEGATIVE") (class "Default")
      (node (ref "C16") (pin "1") (pinfunction "1_1") (pintype "passive"))
      (node (ref "C28") (pin "1") (pinfunction "1_1") (pintype "passive"))
      (node (ref "C32") (pin "1") (pinfunction "1_1") (pintype "passive"))
      (node (ref "C409") (pin "1") (pinfunction "1_1") (pintype "passive"))
      (node (ref "IC6") (pin "4") (pinfunction "OUT_4") (pintype "output"))
      (node (ref "R108") (pin "1") (pinfunction "1_1") (pintype "passive"))
      (node (ref "R31") (pin "2") (pinfunction "2_2") (pintype "passive"))
      (node (ref "R50") (pin "2") (pinfunction "2_2") (pintype "passive"))
      (node (ref "R76") (pin "2") (pinfunction "2_2") (pintype "passive"))
      (node (ref "R78") (pin "2") (pinfunction "2_2") (pintype "passive"))
      (node (ref "R91") (pin "2") (pinfunction "2_2") (pintype "passive"))
      (node (ref "R93") (pin "2") (pinfunction "2_2") (pintype "passive"))
    )
    (net (code "11") (name "AIN1P") (class "Default")
      (node (ref "C12") (pin "1") (pinfunction "1_1") (pintype "passive"))
      (node (ref "R42") (pin "1") (pinfunction "1_1") (pintype "passive"))
      (node (ref "U$2") (pin "35") (pinfunction "AIN1P_35") (pintype "bidirectional"))
    )
    (net (code "12") (name "AIN2P") (class "Default")
      (node (ref "C7") (pin "1") (pinfunction "1_1") (pintype "passive"))
      (node (ref "R30") (pin "1") (pinfunction "1_1") (pintype "passive"))
      (node (ref "U$2") (pin "37") (pinfunction "AIN2P_37") (pintype "bidirectional"))
    )
    (net (code "13") (name "AIN3P") (class "Default")
      (node (ref "C35") (pin "1") (pinfunction "1_1") (pintype "passive"))
      (node (ref "R63") (pin "1") (pinfunction "1_1") (pintype "passive"))
      (node (ref "U$2") (pin "39") (pinfunction "AIN3P_39") (pintype "bidirectional"))
    )
    (net (code "14") (name "AIN4P") (class "Default")
      (node (ref "C37") (pin "1") (pinfunction "1_1") (pintype "passive"))
      (node (ref "R68") (pin "1") (pinfunction "1_1") (pintype "passive"))
      (node (ref "U$2") (pin "41") (pinfunction "AIN4P_41") (pintype "bidirectional"))
    )
    (net (code "15") (name "AIN5P") (class "Default")
      (node (ref "C39") (pin "1") (pinfunction "1_1") (pintype "passive"))
      (node (ref "R67") (pin "1") (pinfunction "1_1") (pintype "passive"))
      (node (ref "U$2") (pin "43") (pinfunction "AIN5P_43") (pintype "bidirectional"))
    )
    (net (code "16") (name "AIN6P") (class "Default")
      (node (ref "C41") (pin "1") (pinfunction "1_1") (pintype "passive"))
      (node (ref "R69") (pin "1") (pinfunction "1_1") (pintype "passive"))
      (node (ref "U$2") (pin "45") (pinfunction "AIN6P_45") (pintype "bidirectional"))
    )
    (net (code "17") (name "AOUT1_N") (class "Default")
      (node (ref "R39") (pin "2") (pinfunction "2_2") (pintype "passive"))
      (node (ref "U$2") (pin "66") (pinfunction "AOUT1N_66") (pintype "bidirectional"))
    )
    (net (code "18") (name "AOUT1_P") (class "Default")
      (node (ref "R45") (pin "2") (pinfunction "2_2") (pintype "passive"))
      (node (ref "U$2") (pin "65") (pinfunction "AOUT1P_65") (pintype "bidirectional"))
    )
    (net (code "19") (name "AOUT2_N") (class "Default")
      (node (ref "R55") (pin "2") (pinfunction "2_2") (pintype "passive"))
      (node (ref "U$2") (pin "64") (pinfunction "AOUT2N_64") (pintype "bidirectional"))
    )
    (net (code "20") (name "AOUT2_P") (class "Default")
      (node (ref "R54") (pin "2") (pinfunction "2_2") (pintype "passive"))
      (node (ref "U$2") (pin "63") (pinfunction "AOUT2P_63") (pintype "bidirectional"))
    )
    (net (code "21") (name "AOUT3_N") (class "Default")
      (node (ref "R89") (pin "2") (pinfunction "2_2") (pintype "passive"))
      (node (ref "U$2") (pin "62") (pinfunction "AOUT3N_62") (pintype "bidirectional"))
    )
    (net (code "22") (name "AOUT3_P") (class "Default")
      (node (ref "R88") (pin "2") (pinfunction "2_2") (pintype "passive"))
      (node (ref "U$2") (pin "61") (pinfunction "AOUT3P_61") (pintype "bidirectional"))
    )
    (net (code "23") (name "AOUT4_N") (class "Default")
      (node (ref "R80") (pin "2") (pinfunction "2_2") (pintype "passive"))
      (node (ref "U$2") (pin "60") (pinfunction "AOUT4N_60") (pintype "bidirectional"))
    )
    (net (code "24") (name "AOUT4_P") (class "Default")
      (node (ref "R79") (pin "2") (pinfunction "2_2") (pintype "passive"))
      (node (ref "U$2") (pin "59") (pinfunction "AOUT4P_59") (pintype "bidirectional"))
    )
    (net (code "25") (name "AOUT5_N") (class "Default")
      (node (ref "R82") (pin "2") (pinfunction "2_2") (pintype "passive"))
      (node (ref "U$2") (pin "58") (pinfunction "AOUT5N_58") (pintype "bidirectional"))
    )
    (net (code "26") (name "AOUT5_P") (class "Default")
      (node (ref "R81") (pin "2") (pinfunction "2_2") (pintype "passive"))
      (node (ref "U$2") (pin "57") (pinfunction "AOUT5P_57") (pintype "bidirectional"))
    )
    (net (code "27") (name "AOUT6_N") (class "Default")
      (node (ref "R95") (pin "2") (pinfunction "2_2") (pintype "passive"))
      (node (ref "U$2") (pin "56") (pinfunction "AOUT6N_56") (pintype "bidirectional"))
    )
    (net (code "28") (name "AOUT6_P") (class "Default")
      (node (ref "R94") (pin "2") (pinfunction "2_2") (pintype "passive"))
      (node (ref "U$2") (pin "55") (pinfunction "AOUT6P_55") (pintype "bidirectional"))
    )
    (net (code "29") (name "AOUT7_N") (class "Default")
      (node (ref "R6") (pin "2") (pinfunction "2_2") (pintype "passive"))
      (node (ref "U$2") (pin "54") (pinfunction "AOUT7N_54") (pintype "bidirectional"))
    )
    (net (code "30") (name "AOUT7_P") (class "Default")
      (node (ref "R5") (pin "2") (pinfunction "2_2") (pintype "passive"))
      (node (ref "U$2") (pin "53") (pinfunction "AOUT7P_53") (pintype "bidirectional"))
    )
    (net (code "31") (name "AOUT8_N") (class "Default")
      (node (ref "R10") (pin "2") (pinfunction "2_2") (pintype "passive"))
      (node (ref "U$2") (pin "52") (pinfunction "AOUT8N_52") (pintype "bidirectional"))
    )
    (net (code "32") (name "AOUT8_P") (class "Default")
      (node (ref "R9") (pin "2") (pinfunction "2_2") (pintype "passive"))
      (node (ref "U$2") (pin "51") (pinfunction "AOUT8P_51") (pintype "bidirectional"))
    )
    (net (code "33") (name "CV1") (class "Default")
      (node (ref "JP14") (pin "5") (pinfunction "5_5") (pintype "passive"))
      (node (ref "R14") (pin "1") (pinfunction "1_1") (pintype "passive"))
    )
    (net (code "34") (name "CV2") (class "Default")
      (node (ref "JP14") (pin "4") (pinfunction "4_4") (pintype "passive"))
      (node (ref "R18") (pin "1") (pinfunction "1_1") (pintype "passive"))
    )
    (net (code "35") (name "CV3") (class "Default")
      (node (ref "JP14") (pin "2") (pinfunction "2_2") (pintype "passive"))
      (node (ref "R26") (pin "1") (pinfunction "1_1") (pintype "passive"))
    )
    (net (code "36") (name "CV4") (class "Default")
      (node (ref "JP14") (pin "1") (pinfunction "1_1") (pintype "passive"))
      (node (ref "R46") (pin "1") (pinfunction "1_1") (pintype "passive"))
    )
    (net (code "37") (name "ENC1A") (class "Default")
      (node (ref "E1") (pin "PINA") (pinfunction "A_PINA") (pintype "bidirectional"))
      (node (ref "JP12") (pin "11") (pinfunction "11_11") (pintype "passive"))
      (node (ref "JP6") (pin "11") (pinfunction "11_11") (pintype "passive"))
      (node (ref "U$2") (pin "19") (pinfunction "TIM4CH1_19") (pintype "bidirectional"))
    )
    (net (code "38") (name "ENC1B") (class "Default")
      (node (ref "E1") (pin "PINB") (pinfunction "B_PINB") (pintype "bidirectional"))
      (node (ref "JP12") (pin "12") (pinfunction "12_12") (pintype "passive"))
      (node (ref "JP6") (pin "12") (pinfunction "12_12") (pintype "passive"))
      (node (ref "U$2") (pin "20") (pinfunction "TIM4CH2_20") (pintype "bidirectional"))
    )
    (net (code "39") (name "ENC1SW") (class "Default")
      (node (ref "E1") (pin "SWITCH2") (pinfunction "S_SWITCH2") (pintype "passive"))
      (node (ref "JP12") (pin "10") (pinfunction "10_10") (pintype "passive"))
      (node (ref "JP6") (pin "10") (pinfunction "10_10") (pintype "passive"))
      (node (ref "U$2") (pin "3") (pinfunction "EXTI8_3") (pintype "bidirectional"))
    )
    (net (code "40") (name "ENC2A") (class "Default")
      (node (ref "E2") (pin "PINA") (pinfunction "A_PINA") (pintype "bidirectional"))
      (node (ref "JP11") (pin "11") (pinfunction "11_11") (pintype "passive"))
      (node (ref "JP7") (pin "11") (pinfunction "11_11") (pintype "passive"))
      (node (ref "U$2") (pin "21") (pinfunction "TIM5CH1_21") (pintype "bidirectional"))
    )
    (net (code "41") (name "ENC2B") (class "Default")
      (node (ref "E2") (pin "PINB") (pinfunction "B_PINB") (pintype "bidirectional"))
      (node (ref "JP11") (pin "12") (pinfunction "12_12") (pintype "passive"))
      (node (ref "JP7") (pin "12") (pinfunction "12_12") (pintype "passive"))
      (node (ref "U$2") (pin "22") (pinfunction "TIM5CH2_22") (pintype "bidirectional"))
    )
    (net (code "42") (name "ENC2SW") (class "Default")
      (node (ref "E2") (pin "SWITCH2") (pinfunction "S_SWITCH2") (pintype "passive"))
      (node (ref "JP11") (pin "10") (pinfunction "10_10") (pintype "passive"))
      (node (ref "JP7") (pin "10") (pinfunction "10_10") (pintype "passive"))
      (node (ref "U$2") (pin "7") (pinfunction "EXTI2_7") (pintype "bidirectional"))
    )
    (net (code "43") (name "ENC3A") (class "Default")
      (node (ref "E3") (pin "PINA") (pinfunction "A_PINA") (pintype "bidirectional"))
      (node (ref "JP10") (pin "11") (pinfunction "11_11") (pintype "passive"))
      (node (ref "JP8") (pin "11") (pinfunction "11_11") (pintype "passive"))
      (node (ref "U$2") (pin "23") (pinfunction "TIM8CH1_23") (pintype "bidirectional"))
    )
    (net (code "44") (name "ENC3B") (class "Default")
      (node (ref "E3") (pin "PINB") (pinfunction "B_PINB") (pintype "bidirectional"))
      (node (ref "JP10") (pin "12") (pinfunction "12_12") (pintype "passive"))
      (node (ref "JP8") (pin "12") (pinfunction "12_12") (pintype "passive"))
      (node (ref "U$2") (pin "24") (pinfunction "TIM8CH2_24") (pintype "bidirectional"))
    )
    (net (code "45") (name "ENC3SW") (class "Default")
      (node (ref "E3") (pin "SWITCH2") (pinfunction "S_SWITCH2") (pintype "passive"))
      (node (ref "JP10") (pin "10") (pinfunction "10_10") (pintype "passive"))
      (node (ref "JP8") (pin "10") (pinfunction "10_10") (pintype "passive"))
      (node (ref "U$2") (pin "9") (pinfunction "EXTI0_9") (pintype "bidirectional"))
    )
    (net (code "46") (name "EXT_RX") (class "Default")
      (node (ref "U$2") (pin "82") (pinfunction "USART3_RX_82") (pintype "bidirectional"))
    )
    (net (code "47") (name "EXT_SCL") (class "Default")
      (node (ref "U$2") (pin "73") (pinfunction "I2C_SCL_73") (pintype "bidirectional"))
    )
    (net (code "48") (name "EXT_SDA") (class "Default")
      (node (ref "U$2") (pin "74") (pinfunction "I2C_SDA_74") (pintype "bidirectional"))
    )
    (net (code "49") (name "EXT_TX") (class "Default")
      (node (ref "U$2") (pin "84") (pinfunction "USART3_TX_84") (pintype "bidirectional"))
    )
    (net (code "50") (name "GND") (class "Default")
      (node (ref "C10") (pin "2") (pinfunction "2_2") (pintype "passive"))
      (node (ref "C12") (pin "2") (pinfunction "2_2") (pintype "passive"))
      (node (ref "C15") (pin "1") (pinfunction "1_1") (pintype "passive"))
      (node (ref "C16") (pin "2") (pinfunction "2_2") (pintype "passive"))
      (node (ref "C19") (pin "2") (pinfunction "2_2") (pintype "passive"))
      (node (ref "C20") (pin "2") (pinfunction "2_2") (pintype "passive"))
      (node (ref "C21") (pin "2") (pinfunction "2_2") (pintype "passive"))
      (node (ref "C22") (pin "2") (pinfunction "2_2") (pintype "passive"))
      (node (ref "C23") (pin "2") (pinfunction "2_2") (pintype "passive"))
      (node (ref "C24") (pin "2") (pinfunction "2_2") (pintype "passive"))
      (node (ref "C25") (pin "2") (pinfunction "2_2") (pintype "passive"))
      (node (ref "C26") (pin "2") (pinfunction "2_2") (pintype "passive"))
      (node (ref "C28") (pin "2") (pinfunction "2_2") (pintype "passive"))
      (node (ref "C29") (pin "1") (pinfunction "1_1") (pintype "passive"))
      (node (ref "C32") (pin "2") (pinfunction "2_2") (pintype "passive"))
      (node (ref "C33") (pin "1") (pinfunction "1_1") (pintype "passive"))
      (node (ref "C35") (pin "2") (pinfunction "2_2") (pintype "passive"))
      (node (ref "C36") (pin "1") (pinfunction "1_1") (pintype "passive"))
      (node (ref "C37") (pin "2") (pinfunction "2_2") (pintype "passive"))
      (node (ref "C38") (pin "1") (pinfunction "1_1") (pintype "passive"))
      (node (ref "C39") (pin "2") (pinfunction "2_2") (pintype "passive"))
      (node (ref "C40") (pin "1") (pinfunction "1_1") (pintype "passive"))
      (node (ref "C409") (pin "2") (pinfunction "2_2") (pintype "passive"))
      (node (ref "C41") (pin "2") (pinfunction "2_2") (pintype "passive"))
      (node (ref "C42") (pin "2") (pinfunction "2_2") (pintype "passive"))
      (node (ref "C5") (pin "1") (pinfunction "1_1") (pintype "passive"))
      (node (ref "C51") (pin "2") (pinfunction "2_2") (pintype "passive"))
      (node (ref "C52") (pin "-") (pinfunction "-_-") (pintype "passive"))
      (node (ref "C53") (pin "-") (pinfunction "-_-") (pintype "passive"))
      (node (ref "C54") (pin "2") (pinfunction "2_2") (pintype "passive"))
      (node (ref "C55") (pin "+") (pinfunction "+_+") (pintype "passive"))
      (node (ref "C57") (pin "2") (pinfunction "2_2") (pintype "passive"))
      (node (ref "C7") (pin "2") (pinfunction "2_2") (pintype "passive"))
      (node (ref "C8") (pin "2") (pinfunction "2_2") (pintype "passive"))
      (node (ref "C9") (pin "1") (pinfunction "1_1") (pintype "passive"))
      (node (ref "CV1") (pin "P$1") (pinfunction "5_P$1") (pintype "passive"))
      (node (ref "CV1") (pin "P$2") (pinfunction "4_P$2") (pintype "passive"))
      (node (ref "CV2") (pin "P$1") (pinfunction "5_P$1") (pintype "passive"))
      (node (ref "CV2") (pin "P$2") (pinfunction "4_P$2") (pintype "passive"))
      (node (ref "CV3") (pin "P$1") (pinfunction "5_P$1") (pintype "passive"))
      (node (ref "CV3") (pin "P$2") (pinfunction "4_P$2") (pintype "passive"))
      (node (ref "CV4") (pin "P$1") (pinfunction "5_P$1") (pintype "passive"))
      (node (ref "CV4") (pin "P$2") (pinfunction "4_P$2") (pintype "passive"))
      (node (ref "D1") (pin "1") (pinfunction "A1_1") (pintype "passive"))
      (node (ref "D2") (pin "1") (pinfunction "A1_1") (pintype "passive"))
      (node (ref "D3") (pin "1") (pinfunction "A1_1") (pintype "passive"))
      (node (ref "D4") (pin "1") (pinfunction "A1_1") (pintype "passive"))
      (node (ref "E1") (pin "C") (pinfunction "C_C") (pintype "bidirectional"))
      (node (ref "E1") (pin "P$1") (pinfunction "P$1_P$1") (pintype "bidirectional"))
      (node (ref "E1") (pin "P$2") (pinfunction "P$1_P$2") (pintype "bidirectional"))
      (node (ref "E1") (pin "SWITCH1") (pinfunction "P_SWITCH1") (pintype "passive"))
      (node (ref "E2") (pin "C") (pinfunction "C_C") (pintype "bidirectional"))
      (node (ref "E2") (pin "P$1") (pinfunction "P$1_P$1") (pintype "bidirectional"))
      (node (ref "E2") (pin "P$2") (pinfunction "P$1_P$2") (pintype "bidirectional"))
      (node (ref "E2") (pin "SWITCH1") (pinfunction "P_SWITCH1") (pintype "passive"))
      (node (ref "E3") (pin "C") (pinfunction "C_C") (pintype "bidirectional"))
      (node (ref "E3") (pin "P$1") (pinfunction "P$1_P$1") (pintype "bidirectional"))
      (node (ref "E3") (pin "P$2") (pinfunction "P$1_P$2") (pintype "bidirectional"))
      (node (ref "E3") (pin "SWITCH1") (pinfunction "P_SWITCH1") (pintype "passive"))
      (node (ref "IC1") (pin "3") (pinfunction "+IN_3") (pintype "input"))
      (node (ref "IC1") (pin "5") (pinfunction "+IN_5") (pintype "input"))
      (node (ref "IC2") (pin "10") (pinfunction "+IN_10") (pintype "input"))
      (node (ref "IC2") (pin "12") (pinfunction "+IN_12") (pintype "input"))
      (node (ref "IC2") (pin "3") (pinfunction "+IN_3") (pintype "input"))
      (node (ref "IC2") (pin "5") (pinfunction "+IN_5") (pintype "input"))
      (node (ref "IC4") (pin "3") (pinfunction "+IN_3") (pintype "input"))
      (node (ref "IC4") (pin "5") (pinfunction "+IN_5") (pintype "input"))
      (node (ref "IC5") (pin "3") (pinfunction "+IN_3") (pintype "input"))
      (node (ref "IC5") (pin "5") (pinfunction "+IN_5") (pintype "input"))
      (node (ref "IC6") (pin "1") (pinfunction "+IN_1") (pintype "input"))
      (node (ref "IC6") (pin "2") (pinfunction "V-_2") (pintype "power_in"))
      (node (ref "IN1") (pin "P$1") (pinfunction "5_P$1") (pintype "passive"))
      (node (ref "IN1") (pin "P$2") (pinfunction "4_P$2") (pintype "passive"))
      (node (ref "IN2") (pin "P$1") (pinfunction "5_P$1") (pintype "passive"))
      (node (ref "IN2") (pin "P$2") (pinfunction "4_P$2") (pintype "passive"))
      (node (ref "IN3") (pin "P$1") (pinfunction "5_P$1") (pintype "passive"))
      (node (ref "IN3") (pin "P$2") (pinfunction "4_P$2") (pintype "passive"))
      (node (ref "IN4") (pin "P$1") (pinfunction "5_P$1") (pintype "passive"))
      (node (ref "IN4") (pin "P$2") (pinfunction "4_P$2") (pintype "passive"))
      (node (ref "IN5") (pin "P$1") (pinfunction "5_P$1") (pintype "passive"))
      (node (ref "IN5") (pin "P$2") (pinfunction "4_P$2") (pintype "passive"))
      (node (ref "IN6") (pin "P$1") (pinfunction "5_P$1") (pintype "passive"))
      (node (ref "IN6") (pin "P$2") (pinfunction "4_P$2") (pintype "passive"))
      (node (ref "JP1") (pin "3") (pinfunction "3_3") (pintype "passive"))
      (node (ref "JP10") (pin "1") (pinfunction "1_1") (pintype "passive"))
      (node (ref "JP11") (pin "1") (pinfunction "1_1") (pintype "passive"))
      (node (ref "JP12") (pin "1") (pinfunction "1_1") (pintype "passive"))
      (node (ref "JP13") (pin "1") (pinfunction "1_1") (pintype "passive"))
      (node (ref "JP13") (pin "12") (pinfunction "12_12") (pintype "passive"))
      (node (ref "JP14") (pin "3") (pinfunction "3_3") (pintype "passive"))
      (node (ref "JP2") (pin "3") (pinfunction "3_3") (pintype "passive"))
      (node (ref "JP3") (pin "6") (pinfunction "6_6") (pintype "passive"))
      (node (ref "JP4") (pin "6") (pinfunction "6_6") (pintype "passive"))
      (node (ref "JP5") (pin "1") (pinfunction "1_1") (pintype "passive"))
      (node (ref "JP5") (pin "12") (pinfunction "12_12") (pintype "passive"))
      (node (ref "JP6") (pin "1") (pinfunction "1_1") (pintype "passive"))
      (node (ref "JP7") (pin "1") (pinfunction "1_1") (pintype "passive"))
      (node (ref "JP8") (pin "1") (pinfunction "1_1") (pintype "passive"))
      (node (ref "JP9") (pin "3") (pinfunction "3_3") (pintype "passive"))
      (node (ref "OUT1") (pin "P$1") (pinfunction "5_P$1") (pintype "passive"))
      (node (ref "OUT2") (pin "P$1") (pinfunction "5_P$1") (pintype "passive"))
      (node (ref "OUT3") (pin "P$1") (pinfunction "5_P$1") (pintype "passive"))
      (node (ref "OUT4") (pin "P$1") (pinfunction "5_P$1") (pintype "passive"))
      (node (ref "OUT5") (pin "P$1") (pinfunction "5_P$1") (pintype "passive"))
      (node (ref "OUT6") (pin "P$1") (pinfunction "5_P$1") (pintype "passive"))
      (node (ref "OUT7") (pin "P$1") (pinfunction "5_P$1") (pintype "passive"))
      (node (ref "OUT8") (pin "P$1") (pinfunction "5_P$1") (pintype "passive"))
      (node (ref "PWR") (pin "3") (pinfunction "3_3") (pintype "passive"))
      (node (ref "PWR") (pin "4") (pinfunction "4_4") (pintype "passive"))
      (node (ref "PWR") (pin "5") (pinfunction "5_5") (pintype "passive"))
      (node (ref "PWR") (pin "6") (pinfunction "6_6") (pintype "passive"))
      (node (ref "PWR") (pin "7") (pinfunction "7_7") (pintype "passive"))
      (node (ref "PWR") (pin "8") (pinfunction "8_8") (pintype "passive"))
      (node (ref "Q1") (pin "2") (pinfunction "E_2") (pintype "passive"))
      (node (ref "Q2") (pin "2") (pinfunction "E_2") (pintype "passive"))
      (node (ref "Q3") (pin "2") (pinfunction "E_2") (pintype "passive"))
      (node (ref "R12") (pin "2") (pinfunction "2_2") (pintype "passive"))
      (node (ref "R24") (pin "2") (pinfunction "2_2") (pintype "passive"))
      (node (ref "R29") (pin "2") (pinfunction "2_2") (pintype "passive"))
      (node (ref "R38") (pin "2") (pinfunction "2_2") (pintype "passive"))
      (node (ref "R41") (pin "2") (pinfunction "2_2") (pintype "passive"))
      (node (ref "R57") (pin "2") (pinfunction "2_2") (pintype "passive"))
      (node (ref "R74") (pin "2") (pinfunction "2_2") (pintype "passive"))
      (node (ref "R8") (pin "2") (pinfunction "2_2") (pintype "passive"))
      (node (ref "R84") (pin "2") (pinfunction "2_2") (pintype "passive"))
      (node (ref "R86") (pin "2") (pinfunction "2_2") (pintype "passive"))
      (node (ref "R97") (pin "2") (pinfunction "2_2") (pintype "passive"))
      (node (ref "SCREEN") (pin "8") (pinfunction "GND_8") (pintype "power_in"))
      (node (ref "SCREEN1") (pin "1") (pinfunction "GND_1") (pintype "power_in"))
      (node (ref "SW1") (pin "3") (pinfunction "P_3") (pintype "passive"))
      (node (ref "SW1") (pin "4") (pinfunction "P1_4") (pintype "passive"))
      (node (ref "SW2") (pin "3") (pinfunction "P_3") (pintype "passive"))
      (node (ref "SW2") (pin "4") (pinfunction "P1_4") (pintype "passive"))
      (node (ref "SW3") (pin "3") (pinfunction "P_3") (pintype "passive"))
      (node (ref "SW3") (pin "4") (pinfunction "P1_4") (pintype "passive"))
      (node (ref "SW4") (pin "P1") (pinfunction "P_P1") (pintype "passive"))
      (node (ref "SW4") (pin "P2") (pinfunction "P_P2") (pintype "passive"))
      (node (ref "SW5") (pin "P1") (pinfunction "P_P1") (pintype "passive"))
      (node (ref "SW5") (pin "P2") (pinfunction "P_P2") (pintype "passive"))
      (node (ref "SW6") (pin "P1") (pinfunction "P_P1") (pintype "passive"))
      (node (ref "SW6") (pin "P2") (pinfunction "P_P2") (pintype "passive"))
      (node (ref "TR1") (pin "P$1") (pinfunction "5_P$1") (pintype "passive"))
      (node (ref "TR1") (pin "P$2") (pinfunction "4_P$2") (pintype "passive"))
      (node (ref "TR2") (pin "P$1") (pinfunction "5_P$1") (pintype "passive"))
      (node (ref "TR2") (pin "P$2") (pinfunction "4_P$2") (pintype "passive"))
      (node (ref "TR3") (pin "P$1") (pinfunction "5_P$1") (pintype "passive"))
      (node (ref "TR3") (pin "P$2") (pinfunction "4_P$2") (pintype "passive"))
      (node (ref "U$2") (pin "15") (pinfunction "GND_15") (pintype "bidirectional"))
      (node (ref "U$2") (pin "16") (pinfunction "GND_16") (pintype "bidirectional"))
      (node (ref "U$2") (pin "33") (pinfunction "AGND_33") (pintype "bidirectional"))
      (node (ref "U$2") (pin "38") (pinfunction "AIN2N_38") (pintype "bidirectional"))
      (node (ref "U$2") (pin "40") (pinfunction "AIN3N_40") (pintype "bidirectional"))
      (node (ref "U$2") (pin "42") (pinfunction "AIN4N_42") (pintype "bidirectional"))
      (node (ref "U$2") (pin "44") (pinfunction "AIN5N_44") (pintype "bidirectional"))
      (node (ref "U$2") (pin "46") (pinfunction "AIN6N_46") (pintype "bidirectional"))
      (node (ref "U$2") (pin "47") (pinfunction "AGND_47") (pintype "bidirectional"))
      (node (ref "U$2") (pin "48") (pinfunction "AGND_48") (pintype "bidirectional"))
      (node (ref "U$2") (pin "49") (pinfunction "AGND_49") (pintype "bidirectional"))
      (node (ref "U$2") (pin "50") (pinfunction "AGND_50") (pintype "bidirectional"))
      (node (ref "U$2") (pin "67") (pinfunction "AGND_67") (pintype "bidirectional"))
      (node (ref "U$2") (pin "71") (pinfunction "AGND_71") (pintype "bidirectional"))
      (node (ref "U$2") (pin "72") (pinfunction "AGND_72") (pintype "bidirectional"))
      (node (ref "U$2") (pin "85") (pinfunction "GND_85") (pintype "bidirectional"))
      (node (ref "U$2") (pin "86") (pinfunction "GND_86") (pintype "bidirectional"))
      (node (ref "U1") (pin "2") (pinfunction "GND_2") (pintype "power_in"))
    )
    (net (code "51") (name "IN1") (class "Default")
      (node (ref "JP6") (pin "4") (pinfunction "4_4") (pintype "passive"))
      (node (ref "R49") (pin "2") (pinfunction "2_2") (pintype "passive"))
    )
    (net (code "52") (name "IN2") (class "Default")
      (node (ref "JP6") (pin "5") (pinfunction "5_5") (pintype "passive"))
      (node (ref "R33") (pin "2") (pinfunction "2_2") (pintype "passive"))
    )
    (net (code "53") (name "IN3") (class "Default")
      (node (ref "JP7") (pin "4") (pinfunction "4_4") (pintype "passive"))
      (node (ref "R70") (pin "2") (pinfunction "2_2") (pintype "passive"))
    )
    (net (code "54") (name "IN4") (class "Default")
      (node (ref "JP7") (pin "5") (pinfunction "5_5") (pintype "passive"))
      (node (ref "R71") (pin "2") (pinfunction "2_2") (pintype "passive"))
    )
    (net (code "55") (name "IN5") (class "Default")
      (node (ref "JP8") (pin "4") (pinfunction "4_4") (pintype "passive"))
      (node (ref "R72") (pin "2") (pinfunction "2_2") (pintype "passive"))
    )
    (net (code "56") (name "IN6") (class "Default")
      (node (ref "JP8") (pin "5") (pinfunction "5_5") (pintype "passive"))
      (node (ref "R73") (pin "2") (pinfunction "2_2") (pintype "passive"))
    )
    (net (code "57") (name "LEDSW4") (class "Default")
      (node (ref "R20") (pin "1") (pinfunction "1_1") (pintype "passive"))
      (node (ref "U$2") (pin "5") (pinfunction "EXTI4_5") (pintype "bidirectional"))
    )
    (net (code "58") (name "LEDSW4A") (class "Default")
      (node (ref "JP12") (pin "9") (pinfunction "9_9") (pintype "passive"))
      (node (ref "JP6") (pin "9") (pinfunction "9_9") (pintype "passive"))
      (node (ref "R20") (pin "2") (pinfunction "2_2") (pintype "passive"))
      (node (ref "SW4") (pin "PL1") (pinfunction "A_PL1") (pintype "passive"))
    )
    (net (code "59") (name "LEDSW4C") (class "Default")
      (node (ref "JP12") (pin "8") (pinfunction "8_8") (pintype "passive"))
      (node (ref "JP6") (pin "8") (pinfunction "8_8") (pintype "passive"))
      (node (ref "SW4") (pin "PL2") (pinfunction "C_PL2") (pintype "passive"))
      (node (ref "U$2") (pin "13") (pinfunction "TIM2CH1_13") (pintype "bidirectional"))
    )
    (net (code "60") (name "LEDSW5") (class "Default")
      (node (ref "R19") (pin "1") (pinfunction "1_1") (pintype "passive"))
      (node (ref "U$2") (pin "28") (pinfunction "ADC6_28") (pintype "bidirectional"))
    )
    (net (code "61") (name "LEDSW5A") (class "Default")
      (node (ref "JP11") (pin "9") (pinfunction "9_9") (pintype "passive"))
      (node (ref "JP7") (pin "9") (pinfunction "9_9") (pintype "passive"))
      (node (ref "R19") (pin "2") (pinfunction "2_2") (pintype "passive"))
      (node (ref "SW5") (pin "PL1") (pinfunction "A_PL1") (pintype "passive"))
    )
    (net (code "62") (name "LEDSW5C") (class "Default")
      (node (ref "JP11") (pin "8") (pinfunction "8_8") (pintype "passive"))
      (node (ref "JP7") (pin "8") (pinfunction "8_8") (pintype "passive"))
      (node (ref "SW5") (pin "PL2") (pinfunction "C_PL2") (pintype "passive"))
      (node (ref "U$2") (pin "30") (pinfunction "ADC7_30") (pintype "bidirectional"))
    )
    (net (code "63") (name "LEDSW6") (class "Default")
      (node (ref "R13") (pin "1") (pinfunction "1_1") (pintype "passive"))
      (node (ref "U$2") (pin "10") (pinfunction "EXTI1_10") (pintype "bidirectional"))
    )
    (net (code "64") (name "LEDSW6A") (class "Default")
      (node (ref "JP10") (pin "9") (pinfunction "9_9") (pintype "passive"))
      (node (ref "JP8") (pin "9") (pinfunction "9_9") (pintype "passive"))
      (node (ref "R13") (pin "2") (pinfunction "2_2") (pintype "passive"))
      (node (ref "SW6") (pin "PL1") (pinfunction "A_PL1") (pintype "passive"))
    )
    (net (code "65") (name "LEDSW6C") (class "Default")
      (node (ref "JP10") (pin "8") (pinfunction "8_8") (pintype "passive"))
      (node (ref "JP8") (pin "8") (pinfunction "8_8") (pintype "passive"))
      (node (ref "SW6") (pin "PL2") (pinfunction "C_PL2") (pintype "passive"))
      (node (ref "U$2") (pin "14") (pinfunction "TIM2CH2_14") (pintype "bidirectional"))
    )
    (net (code "66") (name "Net-(C3-Pad1)") (class "Default")
      (node (ref "C3") (pin "1") (pinfunction "1_1") (pintype "passive"))
      (node (ref "R4") (pin "2") (pinfunction "2_2") (pintype "passive"))
      (node (ref "R5") (pin "1") (pinfunction "1_1") (pintype "passive"))
      (node (ref "R7") (pin "2") (pinfunction "2_2") (pintype "passive"))
    )
    (net (code "67") (name "Net-(C3-Pad2)") (class "Default")
      (node (ref "C3") (pin "2") (pinfunction "2_2") (pintype "passive"))
      (node (ref "R1") (pin "2") (pinfunction "2_2") (pintype "passive"))
      (node (ref "R6") (pin "1") (pinfunction "1_1") (pintype "passive"))
      (node (ref "R8") (pin "1") (pinfunction "1_1") (pintype "passive"))
    )
    (net (code "68") (name "Net-(C4-Pad1)") (class "Default")
      (node (ref "C4") (pin "1") (pinfunction "1_1") (pintype "passive"))
      (node (ref "R11") (pin "2") (pinfunction "2_2") (pintype "passive"))
      (node (ref "R3") (pin "2") (pinfunction "2_2") (pintype "passive"))
      (node (ref "R9") (pin "1") (pinfunction "1_1") (pintype "passive"))
    )
    (net (code "69") (name "Net-(C4-Pad2)") (class "Default")
      (node (ref "C4") (pin "2") (pinfunction "2_2") (pintype "passive"))
      (node (ref "R10") (pin "1") (pinfunction "1_1") (pintype "passive"))
      (node (ref "R12") (pin "1") (pinfunction "1_1") (pintype "passive"))
      (node (ref "R2") (pin "2") (pinfunction "2_2") (pintype "passive"))
    )
    (net (code "70") (name "Net-(C13-Pad1)") (class "Default")
      (node (ref "C13") (pin "1") (pinfunction "1_1") (pintype "passive"))
      (node (ref "R43") (pin "2") (pinfunction "2_2") (pintype "passive"))
      (node (ref "R44") (pin "2") (pinfunction "2_2") (pintype "passive"))
      (node (ref "R45") (pin "1") (pinfunction "1_1") (pintype "passive"))
    )
    (net (code "71") (name "Net-(C13-Pad2)") (class "Default")
      (node (ref "C13") (pin "2") (pinfunction "2_2") (pintype "passive"))
      (node (ref "R37") (pin "2") (pinfunction "2_2") (pintype "passive"))
      (node (ref "R38") (pin "1") (pinfunction "1_1") (pintype "passive"))
      (node (ref "R39") (pin "1") (pinfunction "1_1") (pintype "passive"))
    )
    (net (code "72") (name "Net-(C18-Pad1)") (class "Default")
      (node (ref "C18") (pin "1") (pinfunction "1_1") (pintype "passive"))
      (node (ref "R32") (pin "2") (pinfunction "2_2") (pintype "passive"))
      (node (ref "R54") (pin "1") (pinfunction "1_1") (pintype "passive"))
      (node (ref "R56") (pin "2") (pinfunction "2_2") (pintype "passive"))
    )
    (net (code "73") (name "Net-(C18-Pad2)") (class "Default")
      (node (ref "C18") (pin "2") (pinfunction "2_2") (pintype "passive"))
      (node (ref "R48") (pin "2") (pinfunction "2_2") (pintype "passive"))
      (node (ref "R55") (pin "1") (pinfunction "1_1") (pintype "passive"))
      (node (ref "R57") (pin "1") (pinfunction "1_1") (pintype "passive"))
    )
    (net (code "74") (name "Net-(C43-Pad1)") (class "Default")
      (node (ref "C43") (pin "1") (pinfunction "1_1") (pintype "passive"))
      (node (ref "R61") (pin "2") (pinfunction "2_2") (pintype "passive"))
      (node (ref "R79") (pin "1") (pinfunction "1_1") (pintype "passive"))
      (node (ref "R85") (pin "2") (pinfunction "2_2") (pintype "passive"))
    )
    (net (code "75") (name "Net-(C43-Pad2)") (class "Default")
      (node (ref "C43") (pin "2") (pinfunction "2_2") (pintype "passive"))
      (node (ref "R62") (pin "2") (pinfunction "2_2") (pintype "passive"))
      (node (ref "R80") (pin "1") (pinfunction "1_1") (pintype "passive"))
      (node (ref "R86") (pin "1") (pinfunction "1_1") (pintype "passive"))
    )
    (net (code "76") (name "Net-(C44-Pad1)") (class "Default")
      (node (ref "C44") (pin "1") (pinfunction "1_1") (pintype "passive"))
      (node (ref "R59") (pin "2") (pinfunction "2_2") (pintype "passive"))
      (node (ref "R81") (pin "1") (pinfunction "1_1") (pintype "passive"))
      (node (ref "R83") (pin "2") (pinfunction "2_2") (pintype "passive"))
    )
    (net (code "77") (name "Net-(C44-Pad2)") (class "Default")
      (node (ref "C44") (pin "2") (pinfunction "2_2") (pintype "passive"))
      (node (ref "R64") (pin "2") (pinfunction "2_2") (pintype "passive"))
      (node (ref "R82") (pin "1") (pinfunction "1_1") (pintype "passive"))
      (node (ref "R84") (pin "1") (pinfunction "1_1") (pintype "passive"))
    )
    (net (code "78") (name "Net-(C47-Pad1)") (class "Default")
      (node (ref "C47") (pin "1") (pinfunction "1_1") (pintype "passive"))
      (node (ref "R65") (pin "2") (pinfunction "2_2") (pintype "passive"))
      (node (ref "R94") (pin "1") (pinfunction "1_1") (pintype "passive"))
      (node (ref "R96") (pin "2") (pinfunction "2_2") (pintype "passive"))
    )
    (net (code "79") (name "Net-(C47-Pad2)") (class "Default")
      (node (ref "C47") (pin "2") (pinfunction "2_2") (pintype "passive"))
      (node (ref "R66") (pin "2") (pinfunction "2_2") (pintype "passive"))
      (node (ref "R95") (pin "1") (pinfunction "1_1") (pintype "passive"))
      (node (ref "R97") (pin "1") (pinfunction "1_1") (pintype "passive"))
    )
    (net (code "80") (name "Net-(C48-Pad1)") (class "Default")
      (node (ref "C48") (pin "1") (pinfunction "1_1") (pintype "passive"))
      (node (ref "R58") (pin "2") (pinfunction "2_2") (pintype "passive"))
      (node (ref "R87") (pin "2") (pinfunction "2_2") (pintype "passive"))
      (node (ref "R88") (pin "1") (pinfunction "1_1") (pintype "passive"))
    )
    (net (code "81") (name "Net-(C48-Pad2)") (class "Default")
      (node (ref "C48") (pin "2") (pinfunction "2_2") (pintype "passive"))
      (node (ref "R60") (pin "2") (pinfunction "2_2") (pintype "passive"))
      (node (ref "R74") (pin "1") (pinfunction "1_1") (pintype "passive"))
      (node (ref "R89") (pin "1") (pinfunction "1_1") (pintype "passive"))
    )
    (net (code "82") (name "Net-(CV1-3)") (class "Default")
      (node (ref "CV1") (pin "P$3") (pinfunction "3_P$3") (pintype "passive"))
      (node (ref "JP1") (pin "5") (pinfunction "5_5") (pintype "passive"))
    )
    (net (code "83") (name "Net-(CV2-3)") (class "Default")
      (node (ref "CV2") (pin "P$3") (pinfunction "3_P$3") (pintype "passive"))
      (node (ref "JP1") (pin "4") (pinfunction "4_4") (pintype "passive"))
    )
    (net (code "84") (name "Net-(CV3-3)") (class "Default")
      (node (ref "CV3") (pin "P$3") (pinfunction "3_P$3") (pintype "passive"))
      (node (ref "JP1") (pin "2") (pinfunction "2_2") (pintype "passive"))
    )
    (net (code "85") (name "Net-(CV4-3)") (class "Default")
      (node (ref "CV4") (pin "P$3") (pinfunction "3_P$3") (pintype "passive"))
      (node (ref "JP1") (pin "1") (pinfunction "1_1") (pintype "passive"))
    )
    (net (code "86") (name "Net-(D1-C1A2)") (class "Default")
      (node (ref "D1") (pin "3") (pinfunction "C1A2_3") (pintype "passive"))
      (node (ref "R16") (pin "1") (pinfunction "1_1") (pintype "passive"))
      (node (ref "R17") (pin "2") (pinfunction "2_2") (pintype "passive"))
    )
    (net (code "87") (name "Net-(D2-C1A2)") (class "Default")
      (node (ref "D2") (pin "3") (pinfunction "C1A2_3") (pintype "passive"))
      (node (ref "R22") (pin "1") (pinfunction "1_1") (pintype "passive"))
      (node (ref "R23") (pin "2") (pinfunction "2_2") (pintype "passive"))
    )
    (net (code "88") (name "Net-(D3-C1A2)") (class "Default")
      (node (ref "D3") (pin "3") (pinfunction "C1A2_3") (pintype "passive"))
      (node (ref "R35") (pin "1") (pinfunction "1_1") (pintype "passive"))
      (node (ref "R36") (pin "2") (pinfunction "2_2") (pintype "passive"))
    )
    (net (code "89") (name "Net-(D4-C1A2)") (class "Default")
      (node (ref "D4") (pin "3") (pinfunction "C1A2_3") (pintype "passive"))
      (node (ref "R52") (pin "1") (pinfunction "1_1") (pintype "passive"))
      (node (ref "R53") (pin "2") (pinfunction "2_2") (pintype "passive"))
    )
    (net (code "90") (name "Net-(D5-PadA)") (class "Default")
      (node (ref "D5") (pin "A") (pinfunction "A_A") (pintype "passive"))
      (node (ref "PWR") (pin "1") (pinfunction "1_1") (pintype "passive"))
      (node (ref "PWR") (pin "2") (pinfunction "2_2") (pintype "passive"))
    )
    (net (code "91") (name "Net-(D6-PadC)") (class "Default")
      (node (ref "D6") (pin "C") (pinfunction "C_C") (pintype "passive"))
      (node (ref "PWR") (pin "10") (pinfunction "10_10") (pintype "passive"))
      (node (ref "PWR") (pin "9") (pinfunction "9_9") (pintype "passive"))
    )
    (net (code "92") (name "Net-(IC1A--IN)") (class "Default")
      (node (ref "C6") (pin "1") (pinfunction "1_1") (pintype "passive"))
      (node (ref "IC1") (pin "2") (pinfunction "-IN_2") (pintype "input"))
      (node (ref "R27") (pin "2") (pinfunction "2_2") (pintype "passive"))
      (node (ref "R31") (pin "1") (pinfunction "1_1") (pintype "passive"))
      (node (ref "R33") (pin "1") (pinfunction "1_1") (pintype "passive"))
    )
    (net (code "93") (name "Net-(IC1A-OUT)") (class "Default")
      (node (ref "C6") (pin "2") (pinfunction "2_2") (pintype "passive"))
      (node (ref "IC1") (pin "1") (pinfunction "OUT_1") (pintype "output"))
      (node (ref "R27") (pin "1") (pinfunction "1_1") (pintype "passive"))
      (node (ref "R30") (pin "2") (pinfunction "2_2") (pintype "passive"))
    )
    (net (code "94") (name "Net-(IC1B--IN)") (class "Default")
      (node (ref "C14") (pin "1") (pinfunction "1_1") (pintype "passive"))
      (node (ref "IC1") (pin "6") (pinfunction "-IN_6") (pintype "input"))
      (node (ref "R47") (pin "2") (pinfunction "2_2") (pintype "passive"))
      (node (ref "R49") (pin "1") (pinfunction "1_1") (pintype "passive"))
      (node (ref "R50") (pin "1") (pinfunction "1_1") (pintype "passive"))
    )
    (net (code "95") (name "Net-(IC1B-OUT)") (class "Default")
      (node (ref "C14") (pin "2") (pinfunction "2_2") (pintype "passive"))
      (node (ref "IC1") (pin "7") (pinfunction "OUT_7") (pintype "output"))
      (node (ref "R42") (pin "2") (pinfunction "2_2") (pintype "passive"))
      (node (ref "R47") (pin "1") (pinfunction "1_1") (pintype "passive"))
    )
    (net (code "96") (name "Net-(IC1C-+IN)") (class "Default")
      (node (ref "C5") (pin "2") (pinfunction "2_2") (pintype "passive"))
      (node (ref "IC1") (pin "10") (pinfunction "+IN_10") (pintype "input"))
      (node (ref "R37") (pin "1") (pinfunction "1_1") (pintype "passive"))
    )
    (net (code "97") (name "Net-(IC1C--IN)") (class "Default")
      (node (ref "C11") (pin "1") (pinfunction "1_1") (pintype "passive"))
      (node (ref "IC1") (pin "9") (pinfunction "-IN_9") (pintype "input"))
      (node (ref "R43") (pin "1") (pinfunction "1_1") (pintype "passive"))
    )
    (net (code "98") (name "Net-(IC1C-OUT)") (class "Default")
      (node (ref "C11") (pin "2") (pinfunction "2_2") (pintype "passive"))
      (node (ref "IC1") (pin "8") (pinfunction "OUT_8") (pintype "output"))
      (node (ref "R44") (pin "1") (pinfunction "1_1") (pintype "passive"))
      (node (ref "R98") (pin "2") (pinfunction "2_2") (pintype "passive"))
    )
    (net (code "99") (name "Net-(IC1D-+IN)") (class "Default")
      (node (ref "C9") (pin "2") (pinfunction "2_2") (pintype "passive"))
      (node (ref "IC1") (pin "12") (pinfunction "+IN_12") (pintype "input"))
      (node (ref "R48") (pin "1") (pinfunction "1_1") (pintype "passive"))
    )
    (net (code "100") (name "Net-(IC1D--IN)") (class "Default")
      (node (ref "C17") (pin "1") (pinfunction "1_1") (pintype "passive"))
      (node (ref "IC1") (pin "13") (pinfunction "-IN_13") (pintype "input"))
      (node (ref "R32") (pin "1") (pinfunction "1_1") (pintype "passive"))
    )
    (net (code "101") (name "Net-(IC1D-OUT)") (class "Default")
      (node (ref "C17") (pin "2") (pinfunction "2_2") (pintype "passive"))
      (node (ref "IC1") (pin "14") (pinfunction "OUT_14") (pintype "output"))
      (node (ref "R56") (pin "1") (pinfunction "1_1") (pintype "passive"))
      (node (ref "R99") (pin "2") (pinfunction "2_2") (pintype "passive"))
    )
    (net (code "102") (name "Net-(IC2A--IN)") (class "Default")
      (node (ref "C56") (pin "1") (pinfunction "1_1") (pintype "passive"))
      (node (ref "IC2") (pin "2") (pinfunction "-IN_2") (pintype "input"))
      (node (ref "R14") (pin "2") (pinfunction "2_2") (pintype "passive"))
      (node (ref "R15") (pin "1") (pinfunction "1_1") (pintype "passive"))
    )
    (net (code "103") (name "Net-(IC2A-OUT)") (class "Default")
      (node (ref "C56") (pin "2") (pinfunction "2_2") (pintype "passive"))
      (node (ref "IC2") (pin "1") (pinfunction "OUT_1") (pintype "output"))
      (node (ref "R15") (pin "2") (pinfunction "2_2") (pintype "passive"))
      (node (ref "R16") (pin "2") (pinfunction "2_2") (pintype "passive"))
    )
    (net (code "104") (name "Net-(IC2B--IN)") (class "Default")
      (node (ref "C58") (pin "1") (pinfunction "1_1") (pintype "passive"))
      (node (ref "IC2") (pin "6") (pinfunction "-IN_6") (pintype "input"))
      (node (ref "R18") (pin "2") (pinfunction "2_2") (pintype "passive"))
      (node (ref "R21") (pin "1") (pinfunction "1_1") (pintype "passive"))
    )
    (net (code "105") (name "Net-(IC2B-OUT)") (class "Default")
      (node (ref "C58") (pin "2") (pinfunction "2_2") (pintype "passive"))
      (node (ref "IC2") (pin "7") (pinfunction "OUT_7") (pintype "output"))
      (node (ref "R21") (pin "2") (pinfunction "2_2") (pintype "passive"))
      (node (ref "R22") (pin "2") (pinfunction "2_2") (pintype "passive"))
    )
    (net (code "106") (name "Net-(IC2C--IN)") (class "Default")
      (node (ref "C59") (pin "1") (pinfunction "1_1") (pintype "passive"))
      (node (ref "IC2") (pin "9") (pinfunction "-IN_9") (pintype "input"))
      (node (ref "R26") (pin "2") (pinfunction "2_2") (pintype "passive"))
      (node (ref "R34") (pin "1") (pinfunction "1_1") (pintype "passive"))
    )
    (net (code "107") (name "Net-(IC2C-OUT)") (class "Default")
      (node (ref "C59") (pin "2") (pinfunction "2_2") (pintype "passive"))
      (node (ref "IC2") (pin "8") (pinfunction "OUT_8") (pintype "output"))
      (node (ref "R34") (pin "2") (pinfunction "2_2") (pintype "passive"))
      (node (ref "R35") (pin "2") (pinfunction "2_2") (pintype "passive"))
    )
    (net (code "108") (name "Net-(IC2D--IN)") (class "Default")
      (node (ref "C60") (pin "1") (pinfunction "1_1") (pintype "passive"))
      (node (ref "IC2") (pin "13") (pinfunction "-IN_13") (pintype "input"))
      (node (ref "R46") (pin "2") (pinfunction "2_2") (pintype "passive"))
      (node (ref "R51") (pin "1") (pinfunction "1_1") (pintype "passive"))
    )
    (net (code "109") (name "Net-(IC2D-OUT)") (class "Default")
      (node (ref "C60") (pin "2") (pinfunction "2_2") (pintype "passive"))
      (node (ref "IC2") (pin "14") (pinfunction "OUT_14") (pintype "output"))
      (node (ref "R51") (pin "2") (pinfunction "2_2") (pintype "passive"))
      (node (ref "R52") (pin "2") (pinfunction "2_2") (pintype "passive"))
    )
    (net (code "110") (name "Net-(IC3A-+IN)") (class "Default")
      (node (ref "C38") (pin "2") (pinfunction "2_2") (pintype "passive"))
      (node (ref "IC3") (pin "3") (pinfunction "+IN_3") (pintype "input"))
      (node (ref "R1") (pin "1") (pinfunction "1_1") (pintype "passive"))
    )
    (net (code "111") (name "Net-(IC3A--IN)") (class "Default")
      (node (ref "C1") (pin "1") (pinfunction "1_1") (pintype "passive"))
      (node (ref "IC3") (pin "2") (pinfunction "-IN_2") (pintype "input"))
      (node (ref "R4") (pin "1") (pinfunction "1_1") (pintype "passive"))
    )
    (net (code "112") (name "Net-(IC3A-OUT)") (class "Default")
      (node (ref "C1") (pin "2") (pinfunction "2_2") (pintype "passive"))
      (node (ref "IC3") (pin "1") (pinfunction "OUT_1") (pintype "output"))
      (node (ref "R104") (pin "2") (pinfunction "2_2") (pintype "passive"))
      (node (ref "R7") (pin "1") (pinfunction "1_1") (pintype "passive"))
    )
    (net (code "113") (name "Net-(IC3B-+IN)") (class "Default")
      (node (ref "C40") (pin "2") (pinfunction "2_2") (pintype "passive"))
      (node (ref "IC3") (pin "5") (pinfunction "+IN_5") (pintype "input"))
      (node (ref "R2") (pin "1") (pinfunction "1_1") (pintype "passive"))
    )
    (net (code "114") (name "Net-(IC3B--IN)") (class "Default")
      (node (ref "C2") (pin "1") (pinfunction "1_1") (pintype "passive"))
      (node (ref "IC3") (pin "6") (pinfunction "-IN_6") (pintype "input"))
      (node (ref "R3") (pin "1") (pinfunction "1_1") (pintype "passive"))
    )
    (net (code "115") (name "Net-(IC3B-OUT)") (class "Default")
      (node (ref "C2") (pin "2") (pinfunction "2_2") (pintype "passive"))
      (node (ref "IC3") (pin "7") (pinfunction "OUT_7") (pintype "output"))
      (node (ref "R105") (pin "2") (pinfunction "2_2") (pintype "passive"))
      (node (ref "R11") (pin "1") (pinfunction "1_1") (pintype "passive"))
    )
    (net (code "116") (name "Net-(IC4A--IN)") (class "Default")
      (node (ref "C50") (pin "1") (pinfunction "1_1") (pintype "passive"))
      (node (ref "IC4") (pin "2") (pinfunction "-IN_2") (pintype "input"))
      (node (ref "R71") (pin "1") (pinfunction "1_1") (pintype "passive"))
      (node (ref "R77") (pin "2") (pinfunction "2_2") (pintype "passive"))
      (node (ref "R78") (pin "1") (pinfunction "1_1") (pintype "passive"))
    )
    (net (code "117") (name "Net-(IC4A-OUT)") (class "Default")
      (node (ref "C50") (pin "2") (pinfunction "2_2") (pintype "passive"))
      (node (ref "IC4") (pin "1") (pinfunction "OUT_1") (pintype "output"))
      (node (ref "R68") (pin "2") (pinfunction "2_2") (pintype "passive"))
      (node (ref "R77") (pin "1") (pinfunction "1_1") (pintype "passive"))
    )
    (net (code "118") (name "Net-(IC4B--IN)") (class "Default")
      (node (ref "C49") (pin "1") (pinfunction "1_1") (pintype "passive"))
      (node (ref "IC4") (pin "6") (pinfunction "-IN_6") (pintype "input"))
      (node (ref "R70") (pin "1") (pinfunction "1_1") (pintype "passive"))
      (node (ref "R75") (pin "2") (pinfunction "2_2") (pintype "passive"))
      (node (ref "R76") (pin "1") (pinfunction "1_1") (pintype "passive"))
    )
    (net (code "119") (name "Net-(IC4B-OUT)") (class "Default")
      (node (ref "C49") (pin "2") (pinfunction "2_2") (pintype "passive"))
      (node (ref "IC4") (pin "7") (pinfunction "OUT_7") (pintype "output"))
      (node (ref "R63") (pin "2") (pinfunction "2_2") (pintype "passive"))
      (node (ref "R75") (pin "1") (pinfunction "1_1") (pintype "passive"))
    )
    (net (code "120") (name "Net-(IC4C-+IN)") (class "Default")
      (node (ref "C29") (pin "2") (pinfunction "2_2") (pintype "passive"))
      (node (ref "IC4") (pin "10") (pinfunction "+IN_10") (pintype "input"))
      (node (ref "R60") (pin "1") (pinfunction "1_1") (pintype "passive"))
    )
    (net (code "121") (name "Net-(IC4C--IN)") (class "Default")
      (node (ref "C27") (pin "1") (pinfunction "1_1") (pintype "passive"))
      (node (ref "IC4") (pin "9") (pinfunction "-IN_9") (pintype "input"))
      (node (ref "R58") (pin "1") (pinfunction "1_1") (pintype "passive"))
    )
    (net (code "122") (name "Net-(IC4C-OUT)") (class "Default")
      (node (ref "C27") (pin "2") (pinfunction "2_2") (pintype "passive"))
      (node (ref "IC4") (pin "8") (pinfunction "OUT_8") (pintype "output"))
      (node (ref "R100") (pin "2") (pinfunction "2_2") (pintype "passive"))
      (node (ref "R87") (pin "1") (pinfunction "1_1") (pintype "passive"))
    )
    (net (code "123") (name "Net-(IC4D-+IN)") (class "Default")
      (node (ref "C15") (pin "2") (pinfunction "2_2") (pintype "passive"))
      (node (ref "IC4") (pin "12") (pinfunction "+IN_12") (pintype "input"))
      (node (ref "R62") (pin "1") (pinfunction "1_1") (pintype "passive"))
    )
    (net (code "124") (name "Net-(IC4D--IN)") (class "Default")
      (node (ref "C30") (pin "1") (pinfunction "1_1") (pintype "passive"))
      (node (ref "IC4") (pin "13") (pinfunction "-IN_13") (pintype "input"))
      (node (ref "R61") (pin "1") (pinfunction "1_1") (pintype "passive"))
    )
    (net (code "125") (name "Net-(IC4D-OUT)") (class "Default")
      (node (ref "C30") (pin "2") (pinfunction "2_2") (pintype "passive"))
      (node (ref "IC4") (pin "14") (pinfunction "OUT_14") (pintype "output"))
      (node (ref "R101") (pin "2") (pinfunction "2_2") (pintype "passive"))
      (node (ref "R85") (pin "1") (pinfunction "1_1") (pintype "passive"))
    )
    (net (code "126") (name "Net-(IC5A--IN)") (class "Default")
      (node (ref "C46") (pin "1") (pinfunction "1_1") (pintype "passive"))
      (node (ref "IC5") (pin "2") (pinfunction "-IN_2") (pintype "input"))
      (node (ref "R73") (pin "1") (pinfunction "1_1") (pintype "passive"))
      (node (ref "R92") (pin "2") (pinfunction "2_2") (pintype "passive"))
      (node (ref "R93") (pin "1") (pinfunction "1_1") (pintype "passive"))
    )
    (net (code "127") (name "Net-(IC5A-OUT)") (class "Default")
      (node (ref "C46") (pin "2") (pinfunction "2_2") (pintype "passive"))
      (node (ref "IC5") (pin "1") (pinfunction "OUT_1") (pintype "output"))
      (node (ref "R69") (pin "2") (pinfunction "2_2") (pintype "passive"))
      (node (ref "R92") (pin "1") (pinfunction "1_1") (pintype "passive"))
    )
    (net (code "128") (name "Net-(IC5B--IN)") (class "Default")
      (node (ref "C45") (pin "1") (pinfunction "1_1") (pintype "passive"))
      (node (ref "IC5") (pin "6") (pinfunction "-IN_6") (pintype "input"))
      (node (ref "R72") (pin "1") (pinfunction "1_1") (pintype "passive"))
      (node (ref "R90") (pin "2") (pinfunction "2_2") (pintype "passive"))
      (node (ref "R91") (pin "1") (pinfunction "1_1") (pintype "passive"))
    )
    (net (code "129") (name "Net-(IC5B-OUT)") (class "Default")
      (node (ref "C45") (pin "2") (pinfunction "2_2") (pintype "passive"))
      (node (ref "IC5") (pin "7") (pinfunction "OUT_7") (pintype "output"))
      (node (ref "R67") (pin "2") (pinfunction "2_2") (pintype "passive"))
      (node (ref "R90") (pin "1") (pinfunction "1_1") (pintype "passive"))
    )
    (net (code "130") (name "Net-(IC5C-+IN)") (class "Default")
      (node (ref "C33") (pin "2") (pinfunction "2_2") (pintype "passive"))
      (node (ref "IC5") (pin "10") (pinfunction "+IN_10") (pintype "input"))
      (node (ref "R64") (pin "1") (pinfunction "1_1") (pintype "passive"))
    )
    (net (code "131") (name "Net-(IC5C--IN)") (class "Default")
      (node (ref "C31") (pin "1") (pinfunction "1_1") (pintype "passive"))
      (node (ref "IC5") (pin "9") (pinfunction "-IN_9") (pintype "input"))
      (node (ref "R59") (pin "1") (pinfunction "1_1") (pintype "passive"))
    )
    (net (code "132") (name "Net-(IC5C-OUT)") (class "Default")
      (node (ref "C31") (pin "2") (pinfunction "2_2") (pintype "passive"))
      (node (ref "IC5") (pin "8") (pinfunction "OUT_8") (pintype "output"))
      (node (ref "R102") (pin "2") (pinfunction "2_2") (pintype "passive"))
      (node (ref "R83") (pin "1") (pinfunction "1_1") (pintype "passive"))
    )
    (net (code "133") (name "Net-(IC5D-+IN)") (class "Default")
      (node (ref "C36") (pin "2") (pinfunction "2_2") (pintype "passive"))
      (node (ref "IC5") (pin "12") (pinfunction "+IN_12") (pintype "input"))
      (node (ref "R66") (pin "1") (pinfunction "1_1") (pintype "passive"))
    )
    (net (code "134") (name "Net-(IC5D--IN)") (class "Default")
      (node (ref "C34") (pin "1") (pinfunction "1_1") (pintype "passive"))
      (node (ref "IC5") (pin "13") (pinfunction "-IN_13") (pintype "input"))
      (node (ref "R65") (pin "1") (pinfunction "1_1") (pintype "passive"))
    )
    (net (code "135") (name "Net-(IC5D-OUT)") (class "Default")
      (node (ref "C34") (pin "2") (pinfunction "2_2") (pintype "passive"))
      (node (ref "IC5") (pin "14") (pinfunction "OUT_14") (pintype "output"))
      (node (ref "R103") (pin "2") (pinfunction "2_2") (pintype "passive"))
      (node (ref "R96") (pin "1") (pinfunction "1_1") (pintype "passive"))
    )
    (net (code "136") (name "Net-(IC6--IN)") (class "Default")
      (node (ref "IC6") (pin "3") (pinfunction "-IN_3") (pintype "input"))
      (node (ref "R108") (pin "2") (pinfunction "2_2") (pintype "passive"))
      (node (ref "R109") (pin "1") (pinfunction "1_1") (pintype "passive"))
    )
    (net (code "137") (name "Net-(IN1-3)") (class "Default")
      (node (ref "IN1") (pin "P$3") (pinfunction "3_P$3") (pintype "passive"))
      (node (ref "JP12") (pin "4") (pinfunction "4_4") (pintype "passive"))
    )
    (net (code "138") (name "Net-(IN2-3)") (class "Default")
      (node (ref "IN2") (pin "P$3") (pinfunction "3_P$3") (pintype "passive"))
      (node (ref "JP12") (pin "5") (pinfunction "5_5") (pintype "passive"))
    )
    (net (code "139") (name "Net-(IN3-3)") (class "Default")
      (node (ref "IN3") (pin "P$3") (pinfunction "3_P$3") (pintype "passive"))
      (node (ref "JP11") (pin "4") (pinfunction "4_4") (pintype "passive"))
    )
    (net (code "140") (name "Net-(IN4-3)") (class "Default")
      (node (ref "IN4") (pin "P$3") (pinfunction "3_P$3") (pintype "passive"))
      (node (ref "JP11") (pin "5") (pinfunction "5_5") (pintype "passive"))
    )
    (net (code "141") (name "Net-(IN5-3)") (class "Default")
      (node (ref "IN5") (pin "P$3") (pinfunction "3_P$3") (pintype "passive"))
      (node (ref "JP10") (pin "4") (pinfunction "4_4") (pintype "passive"))
    )
    (net (code "142") (name "Net-(IN6-3)") (class "Default")
      (node (ref "IN6") (pin "P$3") (pinfunction "3_P$3") (pintype "passive"))
      (node (ref "JP10") (pin "5") (pinfunction "5_5") (pintype "passive"))
    )
    (net (code "143") (name "Net-(OUT1-3)") (class "Default")
      (node (ref "JP2") (pin "4") (pinfunction "4_4") (pintype "passive"))
      (node (ref "OUT1") (pin "P$3") (pinfunction "3_P$3") (pintype "passive"))
    )
    (net (code "144") (name "Net-(OUT2-3)") (class "Default")
      (node (ref "JP2") (pin "2") (pinfunction "2_2") (pintype "passive"))
      (node (ref "OUT2") (pin "P$3") (pinfunction "3_P$3") (pintype "passive"))
    )
    (net (code "145") (name "Net-(OUT3-3)") (class "Default")
      (node (ref "JP12") (pin "3") (pinfunction "3_3") (pintype "passive"))
      (node (ref "OUT3") (pin "P$3") (pinfunction "3_P$3") (pintype "passive"))
    )
    (net (code "146") (name "Net-(OUT4-3)") (class "Default")
      (node (ref "JP12") (pin "2") (pinfunction "2_2") (pintype "passive"))
      (node (ref "OUT4") (pin "P$3") (pinfunction "3_P$3") (pintype "passive"))
    )
    (net (code "147") (name "Net-(OUT5-3)") (class "Default")
      (node (ref "JP11") (pin "3") (pinfunction "3_3") (pintype "passive"))
      (node (ref "OUT5") (pin "P$3") (pinfunction "3_P$3") (pintype "passive"))
    )
    (net (code "148") (name "Net-(OUT6-3)") (class "Default")
      (node (ref "JP11") (pin "2") (pinfunction "2_2") (pintype "passive"))
      (node (ref "OUT6") (pin "P$3") (pinfunction "3_P$3") (pintype "passive"))
    )
    (net (code "149") (name "Net-(OUT7-3)") (class "Default")
      (node (ref "JP10") (pin "3") (pinfunction "3_3") (pintype "passive"))
      (node (ref "OUT7") (pin "P$3") (pinfunction "3_P$3") (pintype "passive"))
    )
    (net (code "150") (name "Net-(OUT8-3)") (class "Default")
      (node (ref "JP10") (pin "2") (pinfunction "2_2") (pintype "passive"))
      (node (ref "OUT8") (pin "P$3") (pinfunction "3_P$3") (pintype "passive"))
    )
    (net (code "151") (name "Net-(Q1-B)") (class "Default")
      (node (ref "Q1") (pin "1") (pinfunction "B_1") (pintype "passive"))
      (node (ref "R24") (pin "1") (pinfunction "1_1") (pintype "passive"))
      (node (ref "R25") (pin "2") (pinfunction "2_2") (pintype "passive"))
    )
    (net (code "152") (name "Net-(Q2-B)") (class "Default")
      (node (ref "Q2") (pin "1") (pinfunction "B_1") (pintype "passive"))
      (node (ref "R28") (pin "2") (pinfunction "2_2") (pintype "passive"))
      (node (ref "R29") (pin "1") (pinfunction "1_1") (pintype "passive"))
    )
    (net (code "153") (name "Net-(Q3-B)") (class "Default")
      (node (ref "Q3") (pin "1") (pinfunction "B_1") (pintype "passive"))
      (node (ref "R40") (pin "2") (pinfunction "2_2") (pintype "passive"))
      (node (ref "R41") (pin "1") (pinfunction "1_1") (pintype "passive"))
    )
    (net (code "154") (name "Net-(U$2B-USBD_DM)") (class "Default")
      (node (ref "JP3") (pin "3") (pinfunction "3_3") (pintype "passive"))
      (node (ref "U$2") (pin "91") (pinfunction "USBD_DM_91") (pintype "bidirectional"))
    )
    (net (code "155") (name "Net-(U$2B-USBD_DP)") (class "Default")
      (node (ref "JP3") (pin "4") (pinfunction "4_4") (pintype "passive"))
      (node (ref "U$2") (pin "89") (pinfunction "USBD_DP_89") (pintype "bidirectional"))
    )
    (net (code "156") (name "Net-(U$2B-USBD_ID)") (class "Default")
      (node (ref "JP3") (pin "5") (pinfunction "5_5") (pintype "passive"))
      (node (ref "U$2") (pin "87") (pinfunction "USBD_ID_87") (pintype "bidirectional"))
    )
    (net (code "157") (name "Net-(U$2B-USBD_VBUS)") (class "Default")
      (node (ref "JP3") (pin "2") (pinfunction "2_2") (pintype "passive"))
      (node (ref "U$2") (pin "93") (pinfunction "USBD_VBUS_93") (pintype "bidirectional"))
    )
    (net (code "158") (name "Net-(U$2B-USBH_DM)") (class "Default")
      (node (ref "JP4") (pin "3") (pinfunction "3_3") (pintype "passive"))
      (node (ref "U$2") (pin "92") (pinfunction "USBH_DM_92") (pintype "bidirectional"))
    )
    (net (code "159") (name "Net-(U$2B-USBH_DP)") (class "Default")
      (node (ref "JP4") (pin "4") (pinfunction "4_4") (pintype "passive"))
      (node (ref "U$2") (pin "90") (pinfunction "USBH_DP_90") (pintype "bidirectional"))
    )
    (net (code "160") (name "Net-(U$2B-USBH_ID)") (class "Default")
      (node (ref "JP4") (pin "5") (pinfunction "5_5") (pintype "passive"))
      (node (ref "U$2") (pin "88") (pinfunction "USBH_ID_88") (pintype "bidirectional"))
    )
    (net (code "161") (name "Net-(U$2B-USBH_VBUS)") (class "Default")
      (node (ref "JP4") (pin "2") (pinfunction "2_2") (pintype "passive"))
      (node (ref "U$2") (pin "94") (pinfunction "USBH_VBUS_94") (pintype "bidirectional"))
    )
    (net (code "162") (name "OLED_BLK") (class "Default")
      (node (ref "JP13") (pin "2") (pinfunction "2_2") (pintype "passive"))
      (node (ref "JP5") (pin "2") (pinfunction "2_2") (pintype "passive"))
      (node (ref "SCREEN") (pin "1") (pinfunction "BLK_1") (pintype "bidirectional"))
      (node (ref "SCREEN1") (pin "8") (pinfunction "BLK_8") (pintype "bidirectional"))
      (node (ref "U$2") (pin "77") (pinfunction "SPI4_MISO_77") (pintype "bidirectional"))
    )
    (net (code "163") (name "OLED_CS") (class "Default")
      (node (ref "JP13") (pin "3") (pinfunction "3_3") (pintype "passive"))
      (node (ref "JP5") (pin "3") (pinfunction "3_3") (pintype "passive"))
      (node (ref "SCREEN") (pin "5") (pinfunction "CS_5") (pintype "bidirectional"))
      (node (ref "SCREEN1") (pin "7") (pinfunction "CS_7") (pintype "bidirectional"))
      (node (ref "U$2") (pin "75") (pinfunction "SPI4_MOSI_75") (pintype "bidirectional"))
    )
    (net (code "164") (name "OLED_DC") (class "Default")
      (node (ref "JP13") (pin "4") (pinfunction "4_4") (pintype "passive"))
      (node (ref "JP5") (pin "4") (pinfunction "4_4") (pintype "passive"))
      (node (ref "SCREEN") (pin "6") (pinfunction "DC_6") (pintype "bidirectional"))
      (node (ref "SCREEN1") (pin "6") (pinfunction "DC_6") (pintype "bidirectional"))
      (node (ref "U$2") (pin "78") (pinfunction "SPI3_MISO_78") (pintype "bidirectional"))
    )
    (net (code "165") (name "OLED_MOSI") (class "Default")
      (node (ref "JP13") (pin "6") (pinfunction "6_6") (pintype "passive"))
      (node (ref "JP5") (pin "6") (pinfunction "6_6") (pintype "passive"))
      (node (ref "SCREEN") (pin "3") (pinfunction "D1_3") (pintype "bidirectional"))
      (node (ref "SCREEN1") (pin "4") (pinfunction "D1_4") (pintype "bidirectional"))
      (node (ref "U$2") (pin "76") (pinfunction "SPI3_MOSI_76") (pintype "bidirectional"))
    )
    (net (code "166") (name "OLED_RST") (class "Default")
      (node (ref "JP13") (pin "5") (pinfunction "5_5") (pintype "passive"))
      (node (ref "JP5") (pin "5") (pinfunction "5_5") (pintype "passive"))
      (node (ref "SCREEN") (pin "2") (pinfunction "RES_2") (pintype "bidirectional"))
      (node (ref "SCREEN1") (pin "5") (pinfunction "RES_5") (pintype "bidirectional"))
      (node (ref "U$2") (pin "69") (pinfunction "DAC1_69") (pintype "bidirectional"))
    )
    (net (code "167") (name "OLED_SCK") (class "Default")
      (node (ref "JP13") (pin "7") (pinfunction "7_7") (pintype "passive"))
      (node (ref "JP5") (pin "7") (pinfunction "7_7") (pintype "passive"))
      (node (ref "SCREEN") (pin "4") (pinfunction "D0_4") (pintype "bidirectional"))
      (node (ref "SCREEN1") (pin "3") (pinfunction "D0_3") (pintype "bidirectional"))
      (node (ref "U$2") (pin "80") (pinfunction "SPI3_SCK_80") (pintype "bidirectional"))
    )
    (net (code "168") (name "OUT1") (class "Default")
      (node (ref "JP9") (pin "4") (pinfunction "4_4") (pintype "passive"))
      (node (ref "R104") (pin "1") (pinfunction "1_1") (pintype "passive"))
    )
    (net (code "169") (name "OUT2") (class "Default")
      (node (ref "JP9") (pin "2") (pinfunction "2_2") (pintype "passive"))
      (node (ref "R105") (pin "1") (pinfunction "1_1") (pintype "passive"))
    )
    (net (code "170") (name "OUT3") (class "Default")
      (node (ref "JP6") (pin "3") (pinfunction "3_3") (pintype "passive"))
      (node (ref "R98") (pin "1") (pinfunction "1_1") (pintype "passive"))
    )
    (net (code "171") (name "OUT4") (class "Default")
      (node (ref "JP6") (pin "2") (pinfunction "2_2") (pintype "passive"))
      (node (ref "R99") (pin "1") (pinfunction "1_1") (pintype "passive"))
    )
    (net (code "172") (name "OUT5") (class "Default")
      (node (ref "JP7") (pin "3") (pinfunction "3_3") (pintype "passive"))
      (node (ref "R100") (pin "1") (pinfunction "1_1") (pintype "passive"))
    )
    (net (code "173") (name "OUT6") (class "Default")
      (node (ref "JP7") (pin "2") (pinfunction "2_2") (pintype "passive"))
      (node (ref "R101") (pin "1") (pinfunction "1_1") (pintype "passive"))
    )
    (net (code "174") (name "OUT7") (class "Default")
      (node (ref "JP8") (pin "3") (pinfunction "3_3") (pintype "passive"))
      (node (ref "R102") (pin "1") (pinfunction "1_1") (pintype "passive"))
    )
    (net (code "175") (name "OUT8") (class "Default")
      (node (ref "JP8") (pin "2") (pinfunction "2_2") (pintype "passive"))
      (node (ref "R103") (pin "1") (pinfunction "1_1") (pintype "passive"))
    )
    (net (code "176") (name "SW1") (class "Default")
      (node (ref "JP13") (pin "11") (pinfunction "11_11") (pintype "passive"))
      (node (ref "JP5") (pin "11") (pinfunction "11_11") (pintype "passive"))
      (node (ref "SW1") (pin "1") (pinfunction "S_1") (pintype "passive"))
      (node (ref "SW1") (pin "2") (pinfunction "S1_2") (pintype "passive"))
      (node (ref "U$2") (pin "4") (pinfunction "EXTI14_4") (pintype "bidirectional"))
    )
    (net (code "177") (name "SW2") (class "Default")
      (node (ref "JP13") (pin "10") (pinfunction "10_10") (pintype "passive"))
      (node (ref "JP5") (pin "10") (pinfunction "10_10") (pintype "passive"))
      (node (ref "SW2") (pin "1") (pinfunction "S_1") (pintype "passive"))
      (node (ref "SW2") (pin "2") (pinfunction "S1_2") (pintype "passive"))
      (node (ref "U$2") (pin "6") (pinfunction "EXTI6_6") (pintype "bidirectional"))
    )
    (net (code "178") (name "SW3") (class "Default")
      (node (ref "JP13") (pin "9") (pinfunction "9_9") (pintype "passive"))
      (node (ref "JP5") (pin "9") (pinfunction "9_9") (pintype "passive"))
      (node (ref "SW3") (pin "1") (pinfunction "S_1") (pintype "passive"))
      (node (ref "SW3") (pin "2") (pinfunction "S1_2") (pintype "passive"))
      (node (ref "U$2") (pin "8") (pinfunction "EXTI7_8") (pintype "bidirectional"))
    )
    (net (code "179") (name "SW4") (class "Default")
      (node (ref "JP12") (pin "7") (pinfunction "7_7") (pintype "passive"))
      (node (ref "JP6") (pin "7") (pinfunction "7_7") (pintype "passive"))
      (node (ref "SW4") (pin "P3") (pinfunction "S_P3") (pintype "passive"))
      (node (ref "SW4") (pin "P4") (pinfunction "S_P4") (pintype "passive"))
      (node (ref "U$2") (pin "12") (pinfunction "TIM1CH2_12") (pintype "bidirectional"))
    )
    (net (code "180") (name "SW5") (class "Default")
      (node (ref "JP11") (pin "7") (pinfunction "7_7") (pintype "passive"))
      (node (ref "JP7") (pin "7") (pinfunction "7_7") (pintype "passive"))
      (node (ref "SW5") (pin "P3") (pinfunction "S_P3") (pintype "passive"))
      (node (ref "SW5") (pin "P4") (pinfunction "S_P4") (pintype "passive"))
      (node (ref "U$2") (pin "11") (pinfunction "TIM1CH1_11") (pintype "bidirectional"))
    )
    (net (code "181") (name "SW6") (class "Default")
      (node (ref "JP10") (pin "7") (pinfunction "7_7") (pintype "passive"))
      (node (ref "JP8") (pin "7") (pinfunction "7_7") (pintype "passive"))
      (node (ref "SW6") (pin "P3") (pinfunction "S_P3") (pintype "passive"))
      (node (ref "SW6") (pin "P4") (pinfunction "S_P4") (pintype "passive"))
      (node (ref "U$2") (pin "17") (pinfunction "TIM3CH1_17") (pintype "bidirectional"))
    )
    (net (code "182") (name "TR1") (class "Default")
      (node (ref "Q1") (pin "3") (pinfunction "C_3") (pintype "passive"))
      (node (ref "U$2") (pin "26") (pinfunction "ADC5_26") (pintype "bidirectional"))
    )
    (net (code "183") (name "TR1_OUT") (class "Default")
      (node (ref "JP12") (pin "6") (pinfunction "6_6") (pintype "passive"))
      (node (ref "JP6") (pin "6") (pinfunction "6_6") (pintype "passive"))
      (node (ref "R25") (pin "1") (pinfunction "1_1") (pintype "passive"))
      (node (ref "TR1") (pin "P$3") (pinfunction "3_P$3") (pintype "passive"))
    )
    (net (code "184") (name "TR2") (class "Default")
      (node (ref "Q2") (pin "3") (pinfunction "C_3") (pintype "passive"))
      (node (ref "U$2") (pin "83") (pinfunction "USART2_TX_83") (pintype "bidirectional"))
    )
    (net (code "185") (name "TR2_OUT") (class "Default")
      (node (ref "JP11") (pin "6") (pinfunction "6_6") (pintype "passive"))
      (node (ref "JP7") (pin "6") (pinfunction "6_6") (pintype "passive"))
      (node (ref "R28") (pin "1") (pinfunction "1_1") (pintype "passive"))
      (node (ref "TR2") (pin "P$3") (pinfunction "3_P$3") (pintype "passive"))
    )
    (net (code "186") (name "TR3") (class "Default")
      (node (ref "Q3") (pin "3") (pinfunction "C_3") (pintype "passive"))
      (node (ref "U$2") (pin "81") (pinfunction "USART2_RX_81") (pintype "bidirectional"))
    )
    (net (code "187") (name "TR3_OUT") (class "Default")
      (node (ref "JP10") (pin "6") (pinfunction "6_6") (pintype "passive"))
      (node (ref "JP8") (pin "6") (pinfunction "6_6") (pintype "passive"))
      (node (ref "R40") (pin "1") (pinfunction "1_1") (pintype "passive"))
      (node (ref "TR3") (pin "P$3") (pinfunction "3_P$3") (pintype "passive"))
    )
    (net (code "188") (name "unconnected-(JP2-Pad1)") (class "Default")
      (node (ref "JP2") (pin "1") (pinfunction "1_1") (pintype "passive"))
    )
    (net (code "189") (name "unconnected-(JP2-Pad5)") (class "Default")
      (node (ref "JP2") (pin "5") (pinfunction "5_5") (pintype "passive"))
    )
    (net (code "190") (name "unconnected-(JP9-Pad1)") (class "Default")
      (node (ref "JP9") (pin "1") (pinfunction "1_1") (pintype "passive"))
    )
    (net (code "191") (name "unconnected-(JP9-Pad5)") (class "Default")
      (node (ref "JP9") (pin "5") (pinfunction "5_5") (pintype "passive"))
    )
    (net (code "192") (name "unconnected-(OUT1-4-PadP$2)") (class "Default")
      (node (ref "OUT1") (pin "P$2") (pinfunction "4_P$2") (pintype "passive"))
    )
    (net (code "193") (name "unconnected-(OUT2-4-PadP$2)") (class "Default")
      (node (ref "OUT2") (pin "P$2") (pinfunction "4_P$2") (pintype "passive"))
    )
    (net (code "194") (name "unconnected-(OUT3-4-PadP$2)") (class "Default")
      (node (ref "OUT3") (pin "P$2") (pinfunction "4_P$2") (pintype "passive"))
    )
    (net (code "195") (name "unconnected-(OUT4-4-PadP$2)") (class "Default")
      (node (ref "OUT4") (pin "P$2") (pinfunction "4_P$2") (pintype "passive"))
    )
    (net (code "196") (name "unconnected-(OUT5-4-PadP$2)") (class "Default")
      (node (ref "OUT5") (pin "P$2") (pinfunction "4_P$2") (pintype "passive"))
    )
    (net (code "197") (name "unconnected-(OUT6-4-PadP$2)") (class "Default")
      (node (ref "OUT6") (pin "P$2") (pinfunction "4_P$2") (pintype "passive"))
    )
    (net (code "198") (name "unconnected-(OUT7-4-PadP$2)") (class "Default")
      (node (ref "OUT7") (pin "P$2") (pinfunction "4_P$2") (pintype "passive"))
    )
    (net (code "199") (name "unconnected-(OUT8-4-PadP$2)") (class "Default")
      (node (ref "OUT8") (pin "P$2") (pinfunction "4_P$2") (pintype "passive"))
    )
    (net (code "200") (name "unconnected-(U$2A-ADC8-Pad32)") (class "Default")
      (node (ref "U$2") (pin "32") (pinfunction "ADC8_32") (pintype "bidirectional"))
    )
    (net (code "201") (name "unconnected-(U$2A-AIN1N-Pad36)") (class "Default")
      (node (ref "U$2") (pin "36") (pinfunction "AIN1N_36") (pintype "bidirectional"))
    )
    (net (code "202") (name "unconnected-(U$2A-TIM3CH2-Pad18)") (class "Default")
      (node (ref "U$2") (pin "18") (pinfunction "TIM3CH2_18") (pintype "bidirectional"))
    )
    (net (code "203") (name "unconnected-(U$2B-DAC2-Pad70)") (class "Default")
      (node (ref "U$2") (pin "70") (pinfunction "DAC2_70") (pintype "bidirectional"))
    )
    (net (code "204") (name "unconnected-(U$2B-DACREF-Pad68)") (class "Default")
      (node (ref "U$2") (pin "68") (pinfunction "DACREF_68") (pintype "bidirectional"))
    )
    (net (code "205") (name "unconnected-(U$2B-SPI4_SCK-Pad79)") (class "Default")
      (node (ref "U$2") (pin "79") (pinfunction "SPI4_SCK_79") (pintype "bidirectional"))
    )
  )
)
